# Tractive_System_Board_Rev2.net
KiCad netlist of a schematic drawn in EAGLE
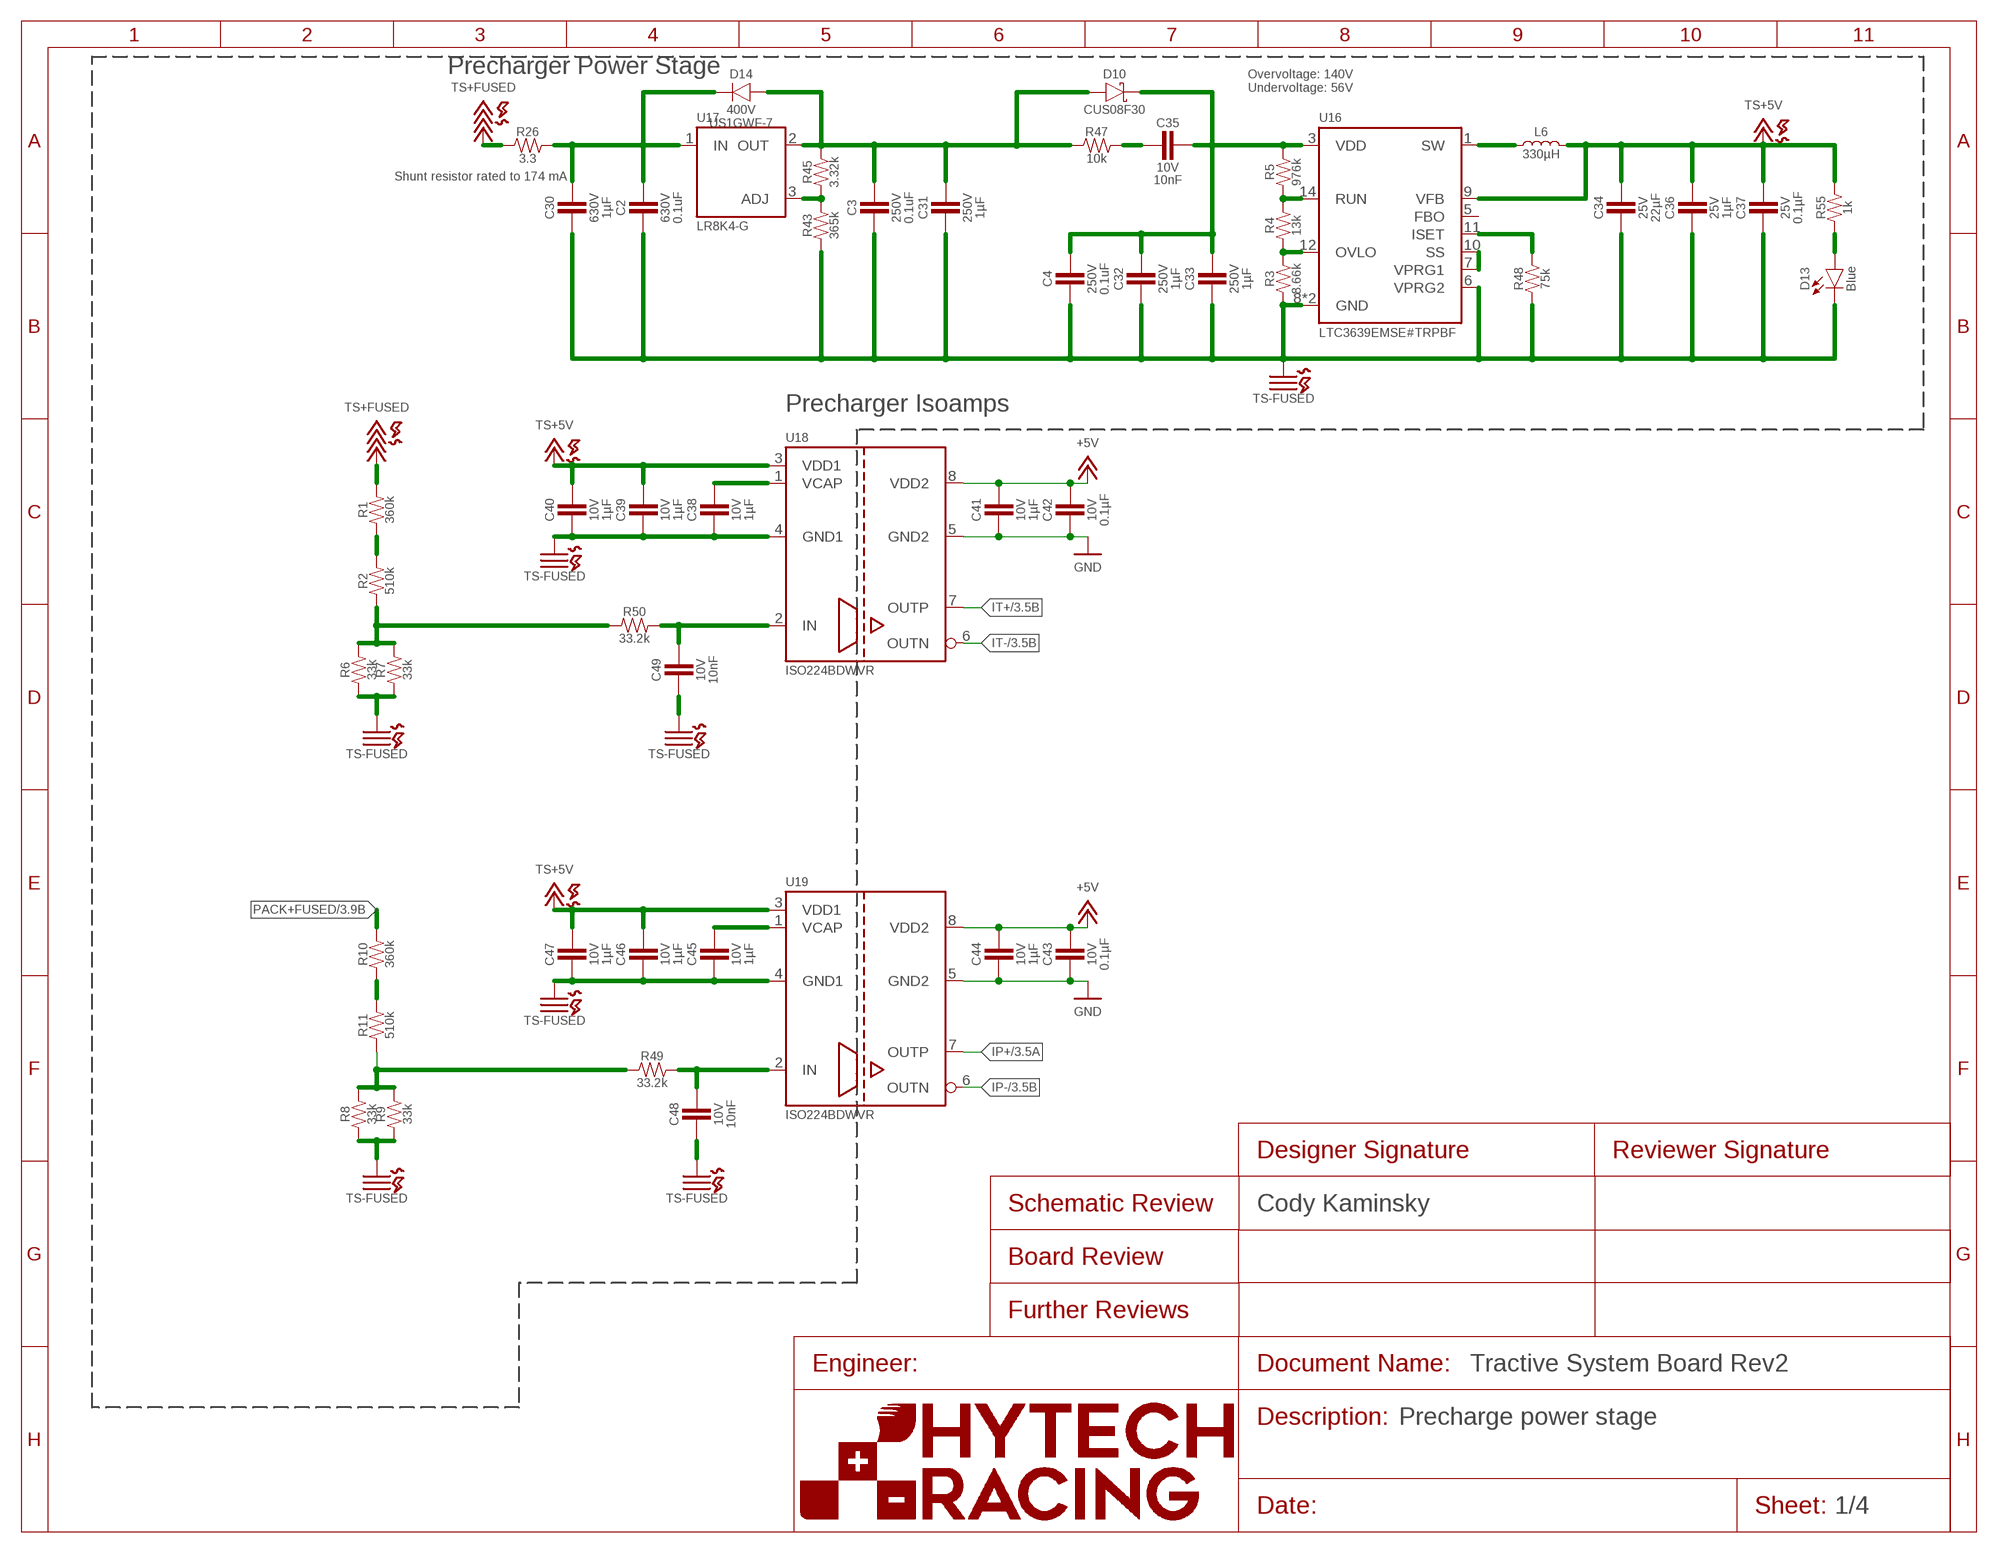
[diagram p0: schematic, sheet 1]
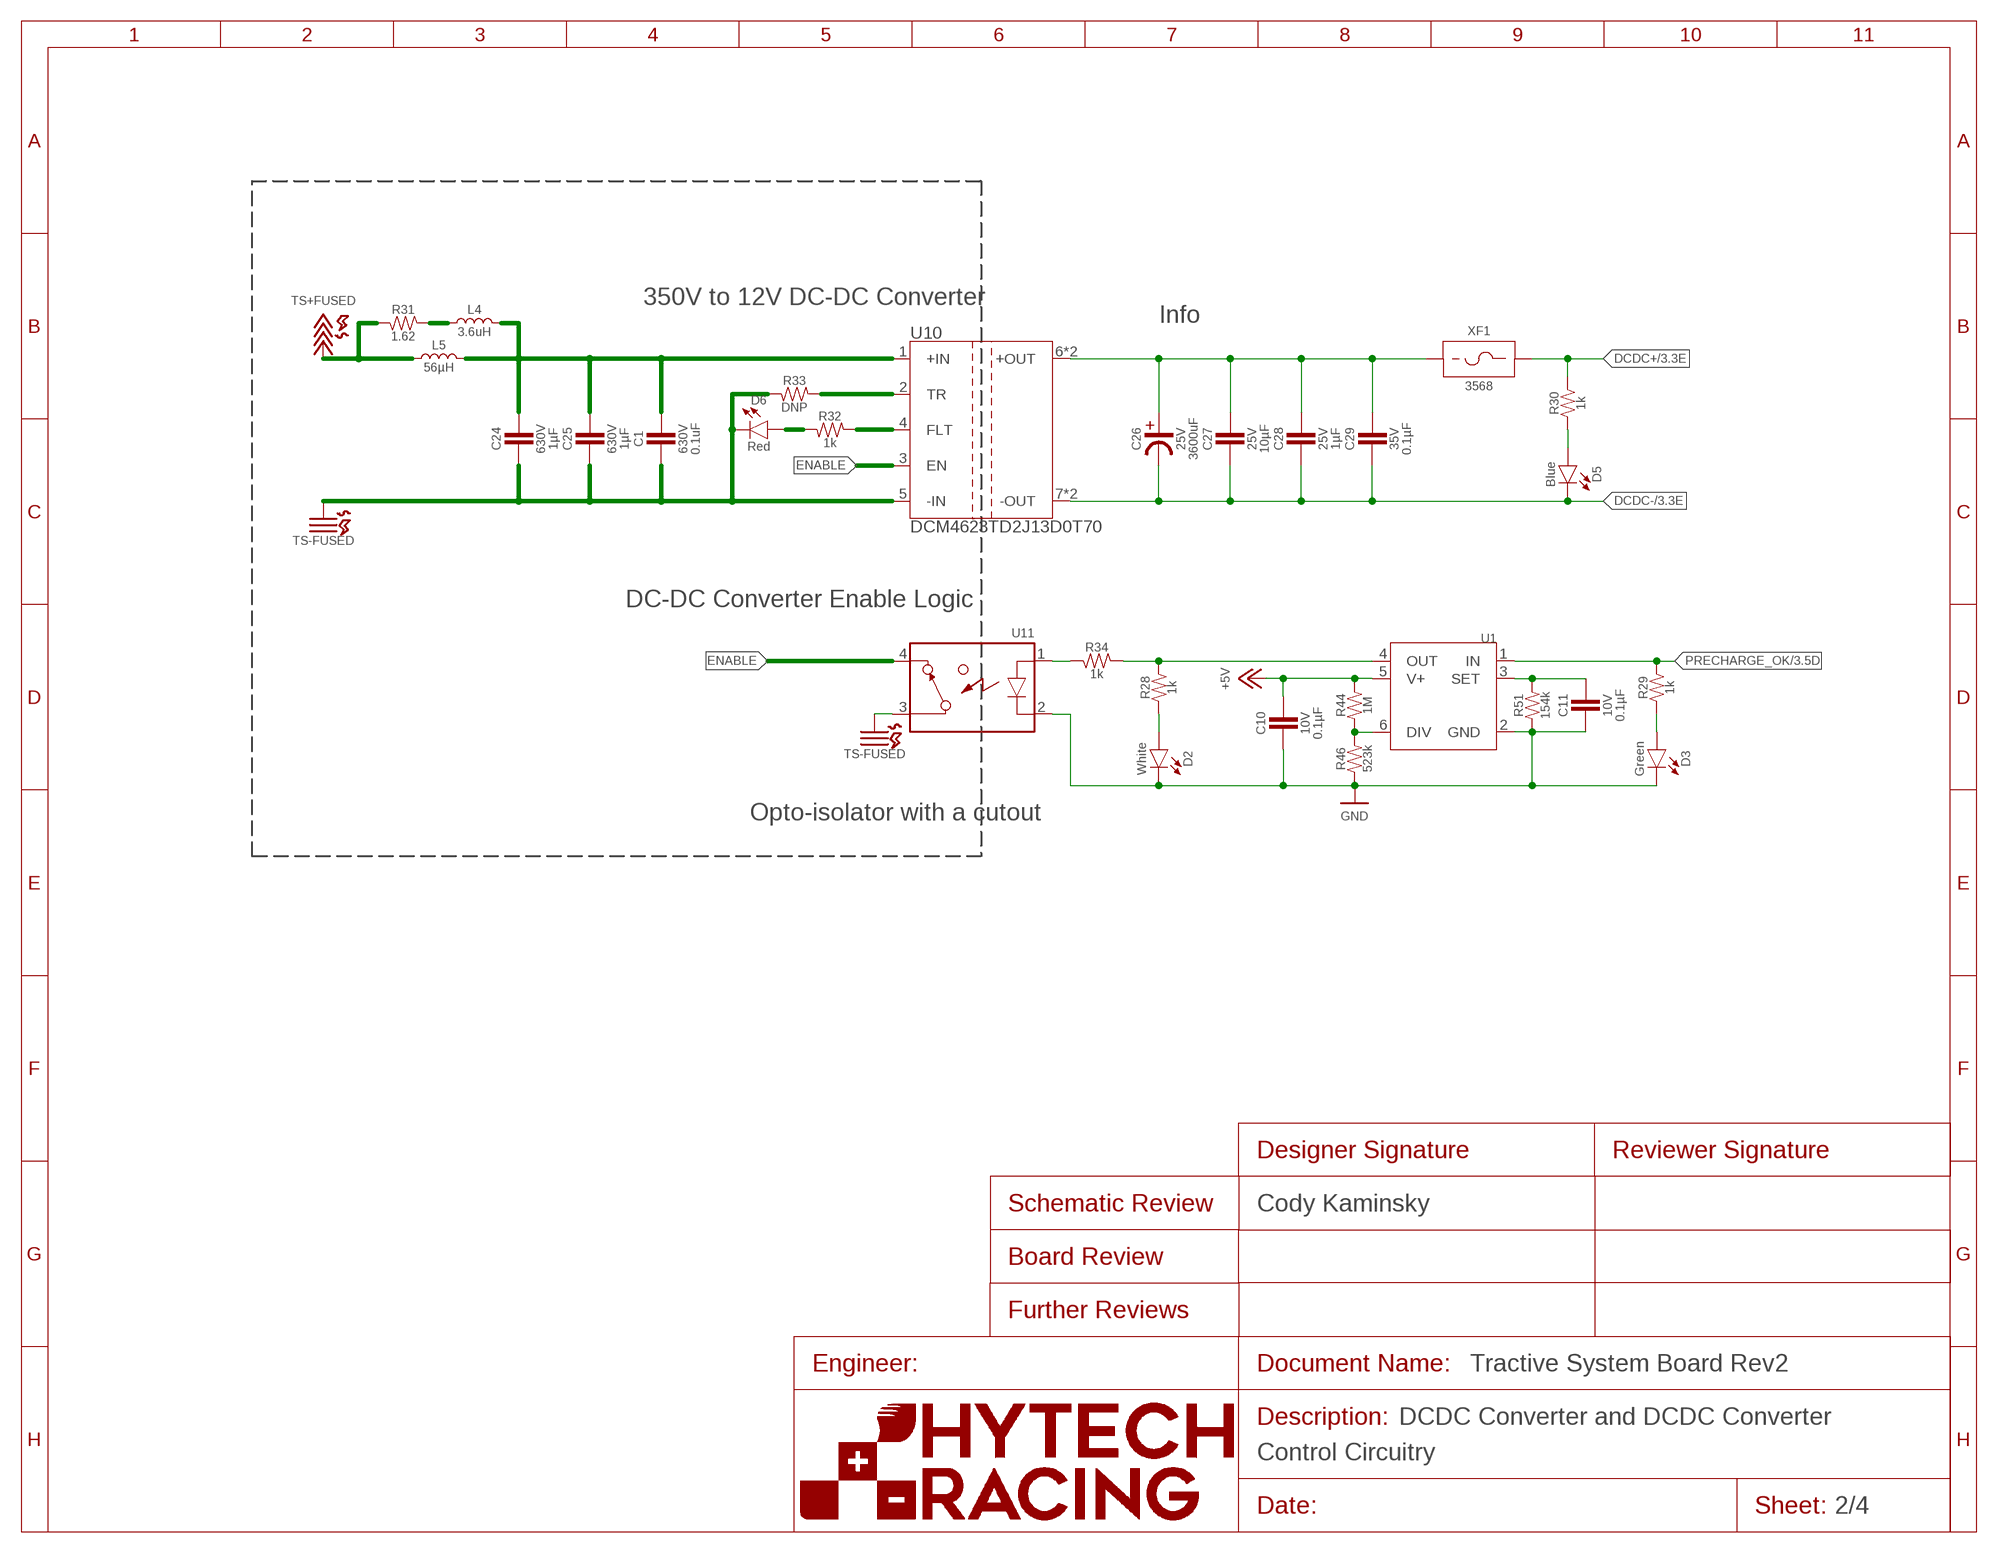
[diagram p1: schematic, sheet 2]
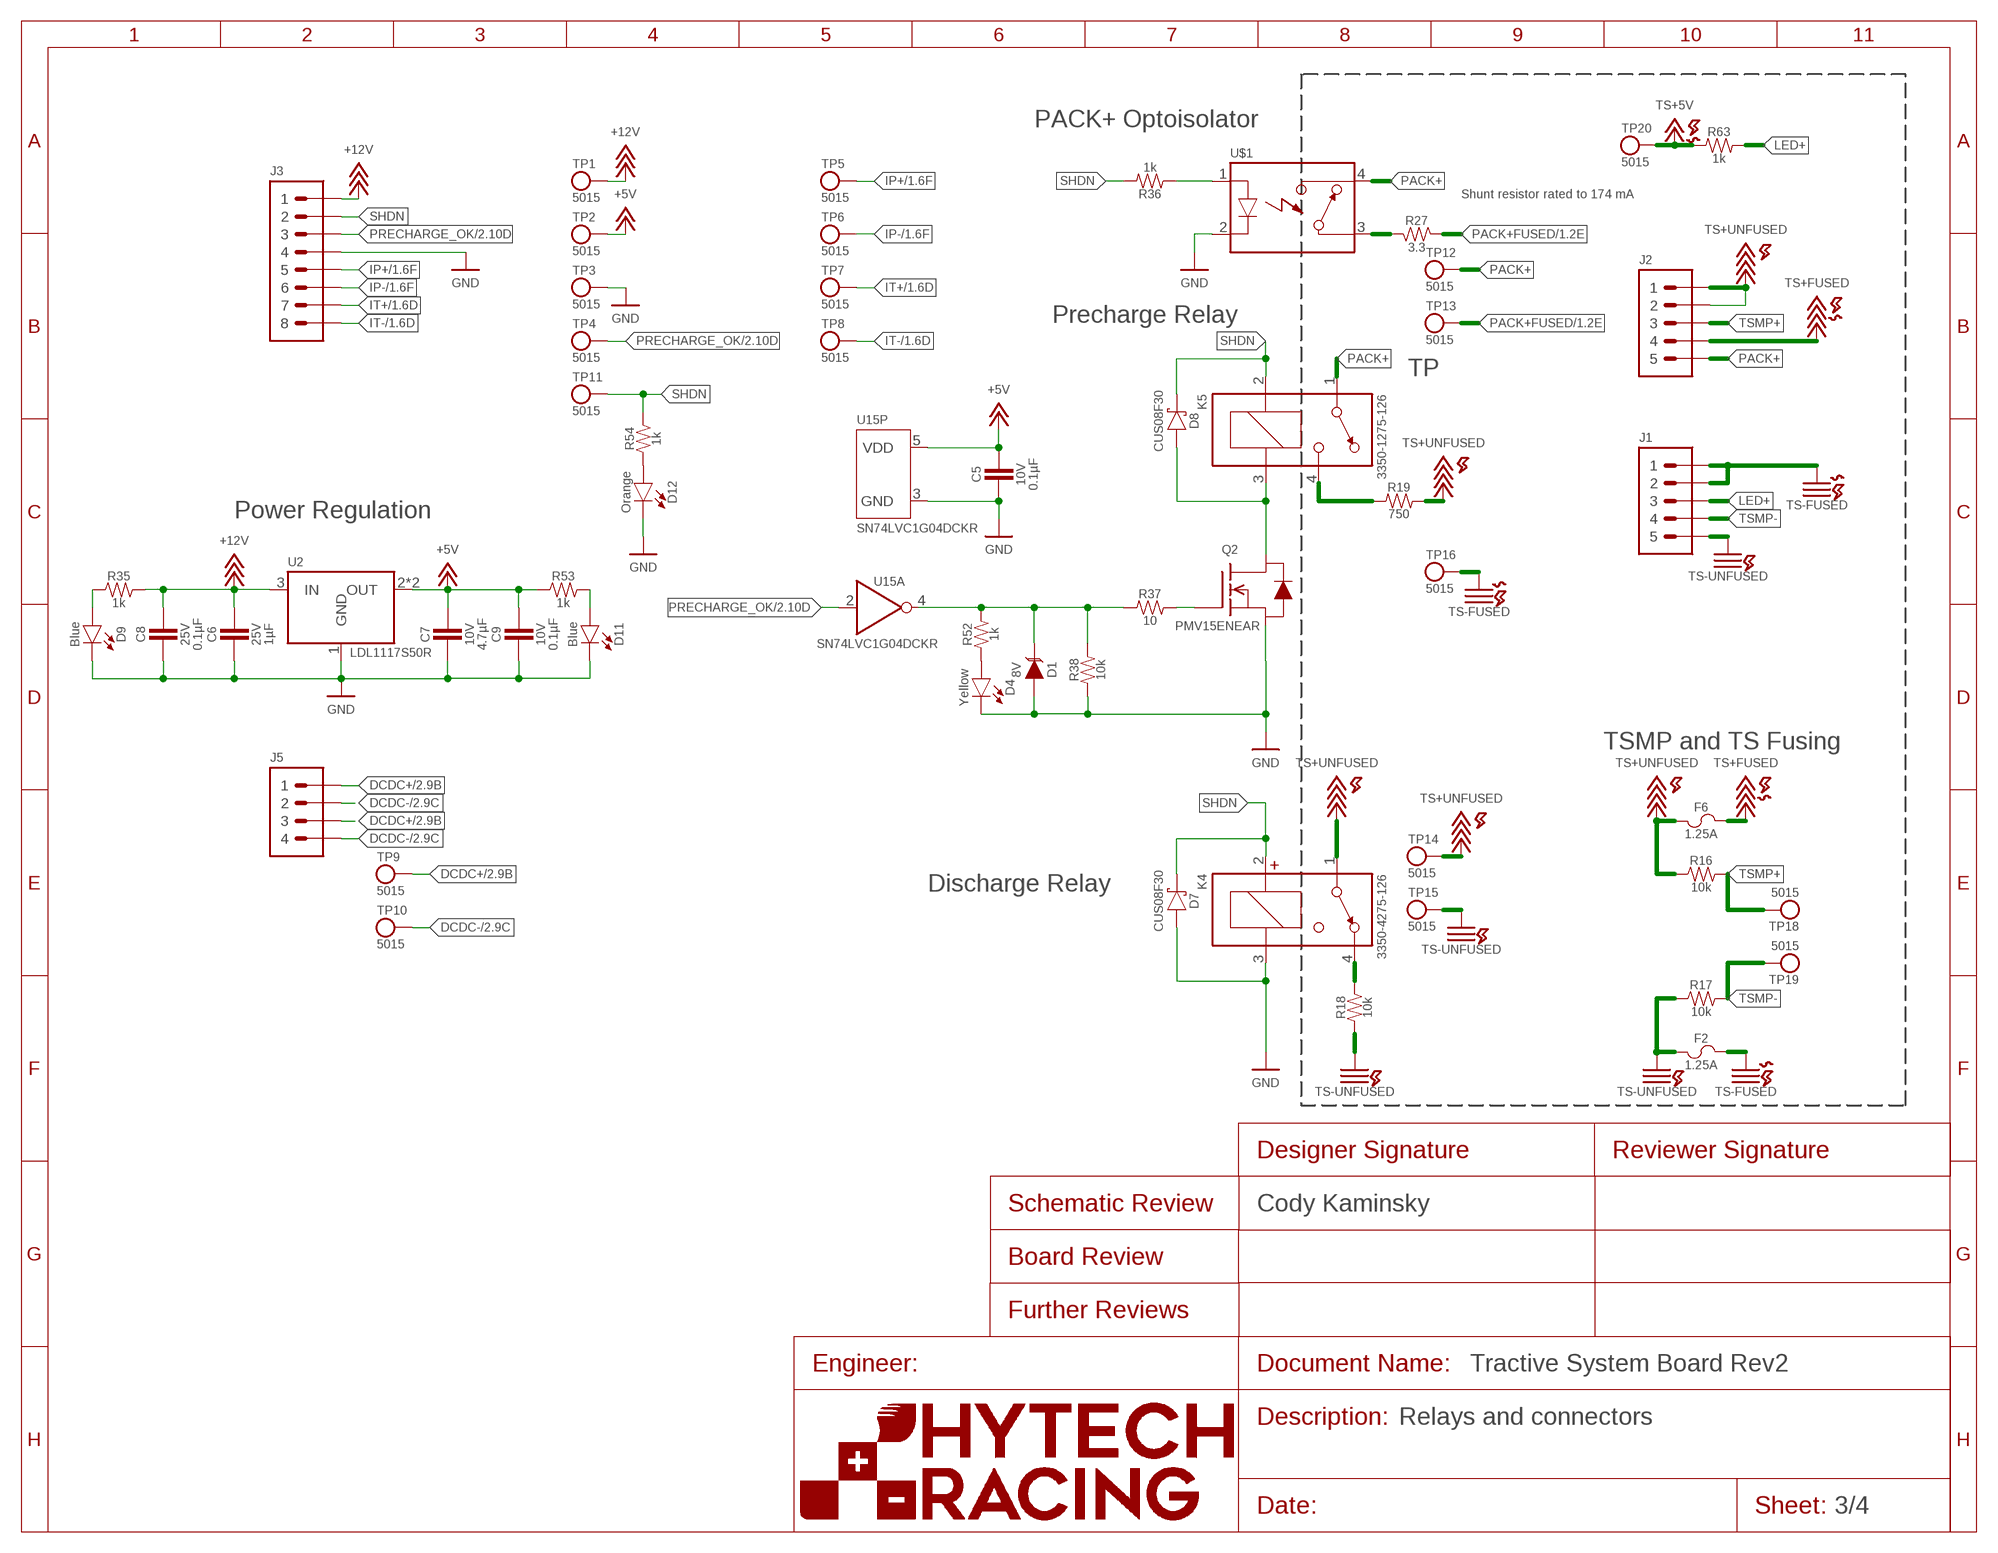
[diagram p2: schematic, sheet 3]
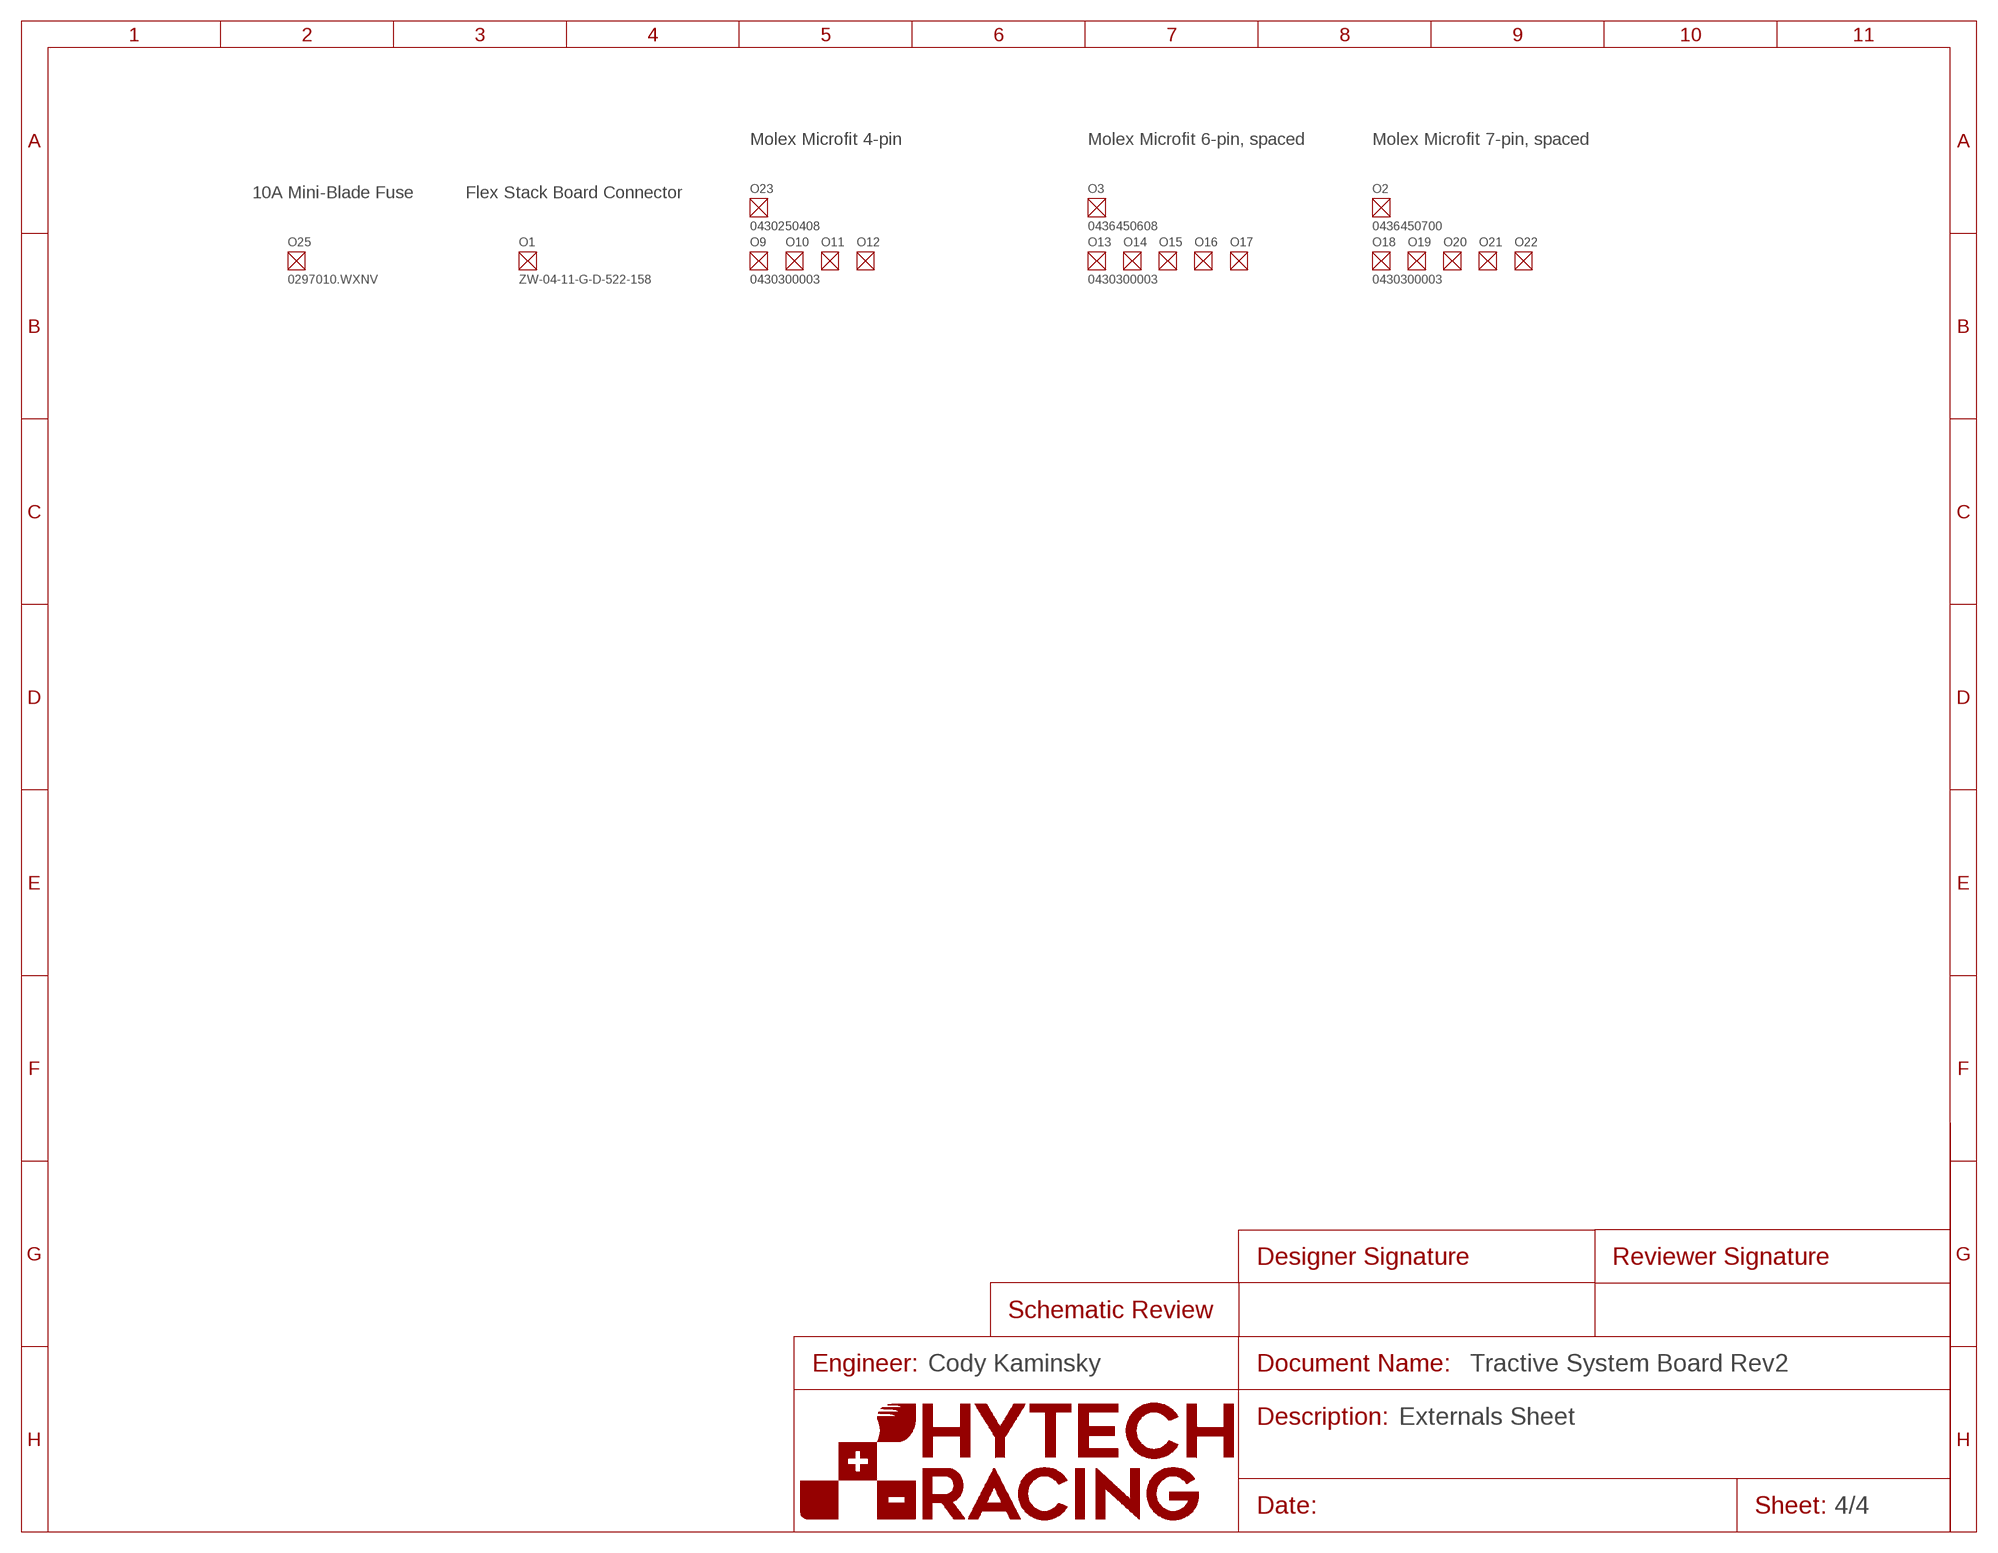
[diagram p3: schematic, sheet 4]

(export (version "E")
  (design (tool "Eeschema 10.0.6"))
  (components
    (comp (ref "C2")
      (value "CAPACITOR_2220_630V_0.1UF")
      (footprint "eagle-import:2220-CAP")
      (fields
        (field (name "CAPACITANCE") "0.1uF")
        (field (name "MANUFACTURER") "TDK Coporation")
        (field (name "MPN") "C5750CH2J104K280KC")
        (field (name "TOLERANCE") "10%")
        (field (name "VOLTAGE") "630V")
      )
      (libsource (lib "eagle-import") (part "CAPACITOR_?_2220630V_0.1UF"))
    )
    (comp (ref "C3")
      (value "CAPACITOR_1206_250V_0.1UF")
      (footprint "eagle-import:1206-CAP")
      (fields
        (field (name "CAPACITANCE") "0.1uF")
        (field (name "MANUFACTURER") "TDK Corporation")
        (field (name "MPN") "C3216X7R2E104K160AM")
        (field (name "TOLERANCE") "10%")
        (field (name "VOLTAGE") "250V")
      )
      (libsource (lib "eagle-import") (part "CAPACITOR_?_1206250V_0.1UF"))
    )
    (comp (ref "C4")
      (value "CAPACITOR_1206_250V_0.1UF")
      (footprint "eagle-import:1206-CAP")
      (fields
        (field (name "CAPACITANCE") "0.1uF")
        (field (name "MANUFACTURER") "TDK Corporation")
        (field (name "MPN") "C3216X7R2E104K160AM")
        (field (name "TOLERANCE") "10%")
        (field (name "VOLTAGE") "250V")
      )
      (libsource (lib "eagle-import") (part "CAPACITOR_?_1206250V_0.1UF"))
    )
    (comp (ref "C30")
      (value "CAPACITOR_2220_630V_1UF")
      (footprint "eagle-import:2220-CAP")
      (fields
        (field (name "CAPACITANCE") "1µF")
        (field (name "MANUFACTURER") "Knowles Syfer")
        (field (name "MPN") "2220Y6300105KXTWS2")
        (field (name "TOLERANCE") "10%")
        (field (name "VOLTAGE") "630V")
      )
      (libsource (lib "eagle-import") (part "CAPACITOR_?_2220630V_1UF"))
    )
    (comp (ref "C31")
      (value "CAPACITOR_2220_250V_1UF")
      (footprint "eagle-import:2220-CAP")
      (fields
        (field (name "CAPACITANCE") "1µF")
        (field (name "MANUFACTURER") "TDK Corporation")
        (field (name "MPN") "C5750X7R2E105K230KA")
        (field (name "TOLERANCE") "10%")
        (field (name "VOLTAGE") "250V")
      )
      (libsource (lib "eagle-import") (part "CAPACITOR_?_2220250V_1UF"))
    )
    (comp (ref "C32")
      (value "CAPACITOR_2220_250V_1UF")
      (footprint "eagle-import:2220-CAP")
      (fields
        (field (name "CAPACITANCE") "1µF")
        (field (name "MANUFACTURER") "TDK Corporation")
        (field (name "MPN") "C5750X7R2E105K230KA")
        (field (name "TOLERANCE") "10%")
        (field (name "VOLTAGE") "250V")
      )
      (libsource (lib "eagle-import") (part "CAPACITOR_?_2220250V_1UF"))
    )
    (comp (ref "C33")
      (value "CAPACITOR_2220_250V_1UF")
      (footprint "eagle-import:2220-CAP")
      (fields
        (field (name "CAPACITANCE") "1µF")
        (field (name "MANUFACTURER") "TDK Corporation")
        (field (name "MPN") "C5750X7R2E105K230KA")
        (field (name "TOLERANCE") "10%")
        (field (name "VOLTAGE") "250V")
      )
      (libsource (lib "eagle-import") (part "CAPACITOR_?_2220250V_1UF"))
    )
    (comp (ref "C34")
      (value "CAPACITOR_0805_25V_22UF")
      (footprint "eagle-import:0805-CAP")
      (fields
        (field (name "CAPACITANCE") "22µF")
        (field (name "MANUFACTURER") "Yageo")
        (field (name "MPN") "CC0805MKX5R8BB226")
        (field (name "TOLERANCE") "20%")
        (field (name "VOLTAGE") "25V")
      )
      (libsource (lib "eagle-import") (part "CAPACITOR_?_080525V_22UF"))
    )
    (comp (ref "C35")
      (value "CAPACITOR_0603_10V_10NF")
      (footprint "eagle-import:0603-CAP")
      (fields
        (field (name "CAPACITANCE") "10nF")
        (field (name "MANUFACTURER") "Yageo")
        (field (name "MPN") "CC0603KRX7R6BB103")
        (field (name "TOLERANCE") "10%")
        (field (name "VOLTAGE") "10V")
      )
      (libsource (lib "eagle-import") (part "CAPACITOR_?_060310V_10NF"))
    )
    (comp (ref "C36")
      (value "CAPACITOR_0603_25V_1UF")
      (footprint "eagle-import:0603-CAP")
      (fields
        (field (name "CAPACITANCE") "1µF")
        (field (name "MANUFACTURER") "Samsung Electro-Mechanics")
        (field (name "MPN") "CL10B105KA8NNNC")
        (field (name "TOLERANCE") "10%")
        (field (name "VOLTAGE") "25V")
      )
      (libsource (lib "eagle-import") (part "CAPACITOR_?_060325V_1UF"))
    )
    (comp (ref "C37")
      (value "CAPACITOR_0603_25V_0.1UF")
      (footprint "eagle-import:0603-CAP")
      (fields
        (field (name "CAPACITANCE") "0.1µF")
        (field (name "MANUFACTURER") "Samsung Electro-Mechanics")
        (field (name "MPN") "CL10B104KA8NNNC")
        (field (name "TOLERANCE") "10%")
        (field (name "VOLTAGE") "25V")
      )
      (libsource (lib "eagle-import") (part "CAPACITOR_?_060325V_0.1UF"))
    )
    (comp (ref "C38")
      (value "CAPACITOR_0603_10V_1UF")
      (footprint "eagle-import:0603-CAP")
      (fields
        (field (name "CAPACITANCE") "1µF")
        (field (name "MANUFACTURER") "Yageo")
        (field (name "MPN") "CC0603KRX7R6BB105")
        (field (name "TOLERANCE") "10%")
        (field (name "VOLTAGE") "10V")
      )
      (libsource (lib "eagle-import") (part "CAPACITOR_?_060310V_1UF"))
    )
    (comp (ref "C39")
      (value "CAPACITOR_0603_10V_1UF")
      (footprint "eagle-import:0603-CAP")
      (fields
        (field (name "CAPACITANCE") "1µF")
        (field (name "MANUFACTURER") "Yageo")
        (field (name "MPN") "CC0603KRX7R6BB105")
        (field (name "TOLERANCE") "10%")
        (field (name "VOLTAGE") "10V")
      )
      (libsource (lib "eagle-import") (part "CAPACITOR_?_060310V_1UF"))
    )
    (comp (ref "C40")
      (value "CAPACITOR_0603_10V_1UF")
      (footprint "eagle-import:0603-CAP")
      (fields
        (field (name "CAPACITANCE") "1µF")
        (field (name "MANUFACTURER") "Yageo")
        (field (name "MPN") "CC0603KRX7R6BB105")
        (field (name "TOLERANCE") "10%")
        (field (name "VOLTAGE") "10V")
      )
      (libsource (lib "eagle-import") (part "CAPACITOR_?_060310V_1UF"))
    )
    (comp (ref "C41")
      (value "CAPACITOR_0603_10V_1UF")
      (footprint "eagle-import:0603-CAP")
      (fields
        (field (name "CAPACITANCE") "1µF")
        (field (name "MANUFACTURER") "Yageo")
        (field (name "MPN") "CC0603KRX7R6BB105")
        (field (name "TOLERANCE") "10%")
        (field (name "VOLTAGE") "10V")
      )
      (libsource (lib "eagle-import") (part "CAPACITOR_?_060310V_1UF"))
    )
    (comp (ref "C42")
      (value "CAPACITOR_0603_10V_0.1UF")
      (footprint "eagle-import:0603-CAP")
      (fields
        (field (name "CAPACITANCE") "0.1µF")
        (field (name "MANUFACTURER") "Vishay Vitramon")
        (field (name "MPN") "VJ0603Y104JXQPW1BC")
        (field (name "TOLERANCE") "5%")
        (field (name "VOLTAGE") "10V")
      )
      (libsource (lib "eagle-import") (part "CAPACITOR_?_060310V_0.1UF"))
    )
    (comp (ref "C43")
      (value "CAPACITOR_0603_10V_0.1UF")
      (footprint "eagle-import:0603-CAP")
      (fields
        (field (name "CAPACITANCE") "0.1µF")
        (field (name "MANUFACTURER") "Vishay Vitramon")
        (field (name "MPN") "VJ0603Y104JXQPW1BC")
        (field (name "TOLERANCE") "5%")
        (field (name "VOLTAGE") "10V")
      )
      (libsource (lib "eagle-import") (part "CAPACITOR_?_060310V_0.1UF"))
    )
    (comp (ref "C44")
      (value "CAPACITOR_0603_10V_1UF")
      (footprint "eagle-import:0603-CAP")
      (fields
        (field (name "CAPACITANCE") "1µF")
        (field (name "MANUFACTURER") "Yageo")
        (field (name "MPN") "CC0603KRX7R6BB105")
        (field (name "TOLERANCE") "10%")
        (field (name "VOLTAGE") "10V")
      )
      (libsource (lib "eagle-import") (part "CAPACITOR_?_060310V_1UF"))
    )
    (comp (ref "C45")
      (value "CAPACITOR_0603_10V_1UF")
      (footprint "eagle-import:0603-CAP")
      (fields
        (field (name "CAPACITANCE") "1µF")
        (field (name "MANUFACTURER") "Yageo")
        (field (name "MPN") "CC0603KRX7R6BB105")
        (field (name "TOLERANCE") "10%")
        (field (name "VOLTAGE") "10V")
      )
      (libsource (lib "eagle-import") (part "CAPACITOR_?_060310V_1UF"))
    )
    (comp (ref "C46")
      (value "CAPACITOR_0603_10V_1UF")
      (footprint "eagle-import:0603-CAP")
      (fields
        (field (name "CAPACITANCE") "1µF")
        (field (name "MANUFACTURER") "Yageo")
        (field (name "MPN") "CC0603KRX7R6BB105")
        (field (name "TOLERANCE") "10%")
        (field (name "VOLTAGE") "10V")
      )
      (libsource (lib "eagle-import") (part "CAPACITOR_?_060310V_1UF"))
    )
    (comp (ref "C47")
      (value "CAPACITOR_0603_10V_1UF")
      (footprint "eagle-import:0603-CAP")
      (fields
        (field (name "CAPACITANCE") "1µF")
        (field (name "MANUFACTURER") "Yageo")
        (field (name "MPN") "CC0603KRX7R6BB105")
        (field (name "TOLERANCE") "10%")
        (field (name "VOLTAGE") "10V")
      )
      (libsource (lib "eagle-import") (part "CAPACITOR_?_060310V_1UF"))
    )
    (comp (ref "C48")
      (value "CAPACITOR_0603_10V_10NF")
      (footprint "eagle-import:0603-CAP")
      (fields
        (field (name "CAPACITANCE") "10nF")
        (field (name "MANUFACTURER") "Yageo")
        (field (name "MPN") "CC0603KRX7R6BB103")
        (field (name "TOLERANCE") "10%")
        (field (name "VOLTAGE") "10V")
      )
      (libsource (lib "eagle-import") (part "CAPACITOR_?_060310V_10NF"))
    )
    (comp (ref "C49")
      (value "CAPACITOR_0603_10V_10NF")
      (footprint "eagle-import:0603-CAP")
      (fields
        (field (name "CAPACITANCE") "10nF")
        (field (name "MANUFACTURER") "Yageo")
        (field (name "MPN") "CC0603KRX7R6BB103")
        (field (name "TOLERANCE") "10%")
        (field (name "VOLTAGE") "10V")
      )
      (libsource (lib "eagle-import") (part "CAPACITOR_?_060310V_10NF"))
    )
    (comp (ref "D10")
      (value "SCHOTTKY_SOD323_30V")
      (footprint "eagle-import:SOD-323")
      (fields
        (field (name "MANUFACTURER") "Toshiba Semiconductor and Storage")
        (field (name "MPN") "CUS08F30")
        (field (name "VOLTAGE") "30V")
      )
      (libsource (lib "eagle-import") (part "SCHOTTKY_?_SOD32330V"))
    )
    (comp (ref "D13")
      (value "LED_0603_BLUE")
      (footprint "eagle-import:0603-LED")
      (fields
        (field (name "COLOR") "Blue")
        (field (name "MANUFACTURER") "Kingbright")
        (field (name "MPN") "APT1608VBC/D")
      )
      (libsource (lib "eagle-import") (part "LED_?_0603BLUE"))
    )
    (comp (ref "D14")
      (value "RECTIFIER_400V_SOD123")
      (footprint "eagle-import:SOD123F")
      (fields
        (field (name "MANUFACTURER") "Diodes Incorporated")
        (field (name "MPN") "US1GWF-7")
        (field (name "VOLTAGE") "400V")
      )
      (libsource (lib "eagle-import") (part "RECTIFIER__?SOD123400V"))
    )
    (comp (ref "L6")
      (value "INDUCTOR_SRU1048_330UH")
      (footprint "eagle-import:SRU1048")
      (fields
        (field (name "INDUCTANCE") "330µH")
        (field (name "MANUFACTURER") "Bourns Inc.")
        (field (name "MPN") "SRU1048-331Y")
        (field (name "TOLERANCE") "30%")
      )
      (libsource (lib "eagle-import") (part "INDUCTOR_?_SRU1048330UH"))
    )
    (comp (ref "R1")
      (value "RESISTOR_0603_360K")
      (footprint "eagle-import:0603-RES")
      (fields
        (field (name "MANUFACTURER") "Rohm Semiconductor")
        (field (name "MPN") "KTR03EZPF3603")
        (field (name "POWER") "0.1W")
        (field (name "RESISTANCE") "360k")
      )
      (libsource (lib "eagle-import") (part "RESISTOR_?_0603360K"))
    )
    (comp (ref "R2")
      (value "RESISTOR_0603_510K")
      (footprint "eagle-import:0603-RES")
      (fields
        (field (name "MANUFACTURER") "Rohm Semiconductor")
        (field (name "MPN") "KTR03EZPF5103")
        (field (name "POWER") "0.1W")
        (field (name "RESISTANCE") "510k")
      )
      (libsource (lib "eagle-import") (part "RESISTOR_?_0603510K"))
    )
    (comp (ref "R3")
      (value "RESISTOR_0603_8.66K")
      (footprint "eagle-import:0603-RES")
      (fields
        (field (name "MANUFACTURER") "Yageo")
        (field (name "MPN") "RT0603BRD078K66L")
        (field (name "POWER") "0.1W")
        (field (name "RESISTANCE") "8.66k")
      )
      (libsource (lib "eagle-import") (part "RESISTOR_?_06038.66K"))
    )
    (comp (ref "R4")
      (value "RESISTOR_0603_13K")
      (footprint "eagle-import:0603-RES")
      (fields
        (field (name "MANUFACTURER") "Panasonic Electronic Components")
        (field (name "MPN") " ERJ-PB3B1302V")
        (field (name "POWER") "0.1W")
        (field (name "RESISTANCE") "13k")
      )
      (libsource (lib "eagle-import") (part "RESISTOR_?_060313K"))
    )
    (comp (ref "R5")
      (value "RESISTOR_0805_976K")
      (footprint "eagle-import:0805-RES")
      (fields
        (field (name "MANUFACTURER") "Panasonic Electronic Components")
        (field (name "MPN") "  ERJ-PB6B9763V")
        (field (name "POWER") "0.25W")
        (field (name "RESISTANCE") "976k")
      )
      (libsource (lib "eagle-import") (part "RESISTOR_?_0805976K"))
    )
    (comp (ref "R6")
      (value "RESISTOR_0603_33K")
      (footprint "eagle-import:0603-RES")
      (fields
        (field (name "MANUFACTURER") "Rohm Semiconductor")
        (field (name "MPN") "KTR03EZPF3302")
        (field (name "POWER") "0.1W")
        (field (name "RESISTANCE") "33k")
      )
      (libsource (lib "eagle-import") (part "RESISTOR_?_060333K"))
    )
    (comp (ref "R7")
      (value "RESISTOR_0603_33K")
      (footprint "eagle-import:0603-RES")
      (fields
        (field (name "MANUFACTURER") "Rohm Semiconductor")
        (field (name "MPN") "KTR03EZPF3302")
        (field (name "POWER") "0.1W")
        (field (name "RESISTANCE") "33k")
      )
      (libsource (lib "eagle-import") (part "RESISTOR_?_060333K"))
    )
    (comp (ref "R8")
      (value "RESISTOR_0603_33K")
      (footprint "eagle-import:0603-RES")
      (fields
        (field (name "MANUFACTURER") "Rohm Semiconductor")
        (field (name "MPN") "KTR03EZPF3302")
        (field (name "POWER") "0.1W")
        (field (name "RESISTANCE") "33k")
      )
      (libsource (lib "eagle-import") (part "RESISTOR_?_060333K"))
    )
    (comp (ref "R9")
      (value "RESISTOR_0603_33K")
      (footprint "eagle-import:0603-RES")
      (fields
        (field (name "MANUFACTURER") "Rohm Semiconductor")
        (field (name "MPN") "KTR03EZPF3302")
        (field (name "POWER") "0.1W")
        (field (name "RESISTANCE") "33k")
      )
      (libsource (lib "eagle-import") (part "RESISTOR_?_060333K"))
    )
    (comp (ref "R10")
      (value "RESISTOR_0603_360K")
      (footprint "eagle-import:0603-RES")
      (fields
        (field (name "MANUFACTURER") "Rohm Semiconductor")
        (field (name "MPN") "KTR03EZPF3603")
        (field (name "POWER") "0.1W")
        (field (name "RESISTANCE") "360k")
      )
      (libsource (lib "eagle-import") (part "RESISTOR_?_0603360K"))
    )
    (comp (ref "R11")
      (value "RESISTOR_0603_510K")
      (footprint "eagle-import:0603-RES")
      (fields
        (field (name "MANUFACTURER") "Rohm Semiconductor")
        (field (name "MPN") "KTR03EZPF5103")
        (field (name "POWER") "0.1W")
        (field (name "RESISTANCE") "510k")
      )
      (libsource (lib "eagle-import") (part "RESISTOR_?_0603510K"))
    )
    (comp (ref "R26")
      (value "RESISTOR_0603_3.3")
      (footprint "eagle-import:0603-RES")
      (fields
        (field (name "MANUFACTURER") "Panasonic Electronic Components")
        (field (name "MPN") "ERJ-3RQF3R3V")
        (field (name "POWER") "0.1W")
        (field (name "RESISTANCE") "3.3")
      )
      (libsource (lib "eagle-import") (part "RESISTOR_?_06033.3"))
    )
    (comp (ref "R43")
      (value "RESISTOR_0805_HV365K")
      (footprint "eagle-import:0805-RES")
      (fields
        (field (name "MANUFACTURER") "Rohm")
        (field (name "MPN") "KTR10EZPF3653")
        (field (name "POWER") "0.125W")
        (field (name "RESISTANCE") "365k")
      )
      (libsource (lib "eagle-import") (part "RESISTOR_?_0805HV365K"))
    )
    (comp (ref "R45")
      (value "RESISTOR_0603_3.32K")
      (footprint "eagle-import:0603-RES")
      (fields
        (field (name "MANUFACTURER") "Yageo")
        (field (name "MPN") "RT0603BRD073K32L")
        (field (name "POWER") "0.1W")
        (field (name "RESISTANCE") "3.32k")
      )
      (libsource (lib "eagle-import") (part "RESISTOR_?_06033.32K"))
    )
    (comp (ref "R47")
      (value "RESISTOR_0603_10K")
      (footprint "eagle-import:0603-RES")
      (fields
        (field (name "MANUFACTURER") "Yageo")
        (field (name "MPN") "RC0603FR-0710KL")
        (field (name "POWER") "0.1W")
        (field (name "RESISTANCE") "10k")
      )
      (libsource (lib "eagle-import") (part "RESISTOR_?_060310K"))
    )
    (comp (ref "R48")
      (value "RESISTOR_0603_75K")
      (footprint "eagle-import:0603-RES")
      (fields
        (field (name "MANUFACTURER") "Yageo")
        (field (name "MPN") "RT0603BRE0775KL")
        (field (name "POWER") "0.1W")
        (field (name "RESISTANCE") "75k")
      )
      (libsource (lib "eagle-import") (part "RESISTOR_?_060375K"))
    )
    (comp (ref "R49")
      (value "RESISTOR_0603_33.2K")
      (footprint "eagle-import:0603-RES")
      (fields
        (field (name "MANUFACTURER") "Panasonic Electronic Components")
        (field (name "MPN") "ERJ-PB3B3322V")
        (field (name "POWER") "0.1W")
        (field (name "RESISTANCE") "33.2k")
      )
      (libsource (lib "eagle-import") (part "RESISTOR_?_060333.2K"))
    )
    (comp (ref "R50")
      (value "RESISTOR_0603_33.2K")
      (footprint "eagle-import:0603-RES")
      (fields
        (field (name "MANUFACTURER") "Panasonic Electronic Components")
        (field (name "MPN") "ERJ-PB3B3322V")
        (field (name "POWER") "0.1W")
        (field (name "RESISTANCE") "33.2k")
      )
      (libsource (lib "eagle-import") (part "RESISTOR_?_060333.2K"))
    )
    (comp (ref "R55")
      (value "RESISTOR_0603_1K")
      (footprint "eagle-import:0603-RES")
      (fields
        (field (name "MANUFACTURER") "Yageo")
        (field (name "MPN") "RC0603FR-071KL")
        (field (name "POWER") "0.1W")
        (field (name "RESISTANCE") "1k")
      )
      (libsource (lib "eagle-import") (part "RESISTOR_?_06031K"))
    )
    (comp (ref "U16")
      (value "LTC3639")
      (footprint "eagle-import:MSE16(12)")
      (fields (field (name "MPN") "LTC3639EMSE#TRPBF ") (field (name "MANUFACTURER") "Analog Devices Inc."))
      (libsource (lib "eagle-import") (part "LTC3639"))
    )
    (comp (ref "U17")
      (value "VOLTAGE_REGULATOR_ADJ_LR8_DPAK")
      (footprint "eagle-import:DPAK(2-7K1S)")
      (fields (field (name "MANUFACTURER") "Microchip Technology") (field (name "MPN") "LR8K4-G"))
      (libsource (lib "eagle-import") (part "VOLTAGE_REGULATOR_ADJ__?DPAKLR8"))
    )
    (comp (ref "U18")
      (value "ISO224B_AIRGAP")
      (footprint "eagle-import:SOIC-08(WIDE,0.295_)-AIRGAP")
      (fields (field (name "MANUFACTURER") "Texas Instruments") (field (name "MPN") "ISO224BDWVR"))
      (libsource (lib "eagle-import") (part "ISO224_AIRGAPB"))
    )
    (comp (ref "U19")
      (value "ISO224B_AIRGAP")
      (footprint "eagle-import:SOIC-08(WIDE,0.295_)-AIRGAP")
      (fields (field (name "MANUFACTURER") "Texas Instruments") (field (name "MPN") "ISO224BDWVR"))
      (libsource (lib "eagle-import") (part "ISO224_AIRGAPB"))
    )
    (comp (ref "C5")
      (value "CAPACITOR_0603_10V_0.1UF")
      (footprint "eagle-import:0603-CAP")
      (fields
        (field (name "CAPACITANCE") "0.1µF")
        (field (name "MANUFACTURER") "Vishay Vitramon")
        (field (name "MPN") "VJ0603Y104JXQPW1BC")
        (field (name "TOLERANCE") "5%")
        (field (name "VOLTAGE") "10V")
      )
      (libsource (lib "eagle-import") (part "CAPACITOR_?_060310V_0.1UF"))
    )
    (comp (ref "C6")
      (value "CAPACITOR_0603_25V_1UF")
      (footprint "eagle-import:0603-CAP")
      (fields
        (field (name "CAPACITANCE") "1µF")
        (field (name "MANUFACTURER") "Samsung Electro-Mechanics")
        (field (name "MPN") "CL10B105KA8NNNC")
        (field (name "TOLERANCE") "10%")
        (field (name "VOLTAGE") "25V")
      )
      (libsource (lib "eagle-import") (part "CAPACITOR_?_060325V_1UF"))
    )
    (comp (ref "C7")
      (value "CAPACITOR_0603_10V_4.7UF")
      (footprint "eagle-import:0603-CAP")
      (fields
        (field (name "CAPACITANCE") "4.7µF")
        (field (name "MANUFACTURER") "Samsung Electro-Mechanics")
        (field (name "MPN") "CL10A475KP8NNNC")
        (field (name "TOLERANCE") "10%")
        (field (name "VOLTAGE") "10V")
      )
      (libsource (lib "eagle-import") (part "CAPACITOR_?_060310V_4.7UF"))
    )
    (comp (ref "C8")
      (value "CAPACITOR_0603_25V_0.1UF")
      (footprint "eagle-import:0603-CAP")
      (fields
        (field (name "CAPACITANCE") "0.1µF")
        (field (name "MANUFACTURER") "Samsung Electro-Mechanics")
        (field (name "MPN") "CL10B104KA8NNNC")
        (field (name "TOLERANCE") "10%")
        (field (name "VOLTAGE") "25V")
      )
      (libsource (lib "eagle-import") (part "CAPACITOR_?_060325V_0.1UF"))
    )
    (comp (ref "C9")
      (value "CAPACITOR_0603_10V_0.1UF")
      (footprint "eagle-import:0603-CAP")
      (fields
        (field (name "CAPACITANCE") "0.1µF")
        (field (name "MANUFACTURER") "Vishay Vitramon")
        (field (name "MPN") "VJ0603Y104JXQPW1BC")
        (field (name "TOLERANCE") "5%")
        (field (name "VOLTAGE") "10V")
      )
      (libsource (lib "eagle-import") (part "CAPACITOR_?_060310V_0.1UF"))
    )
    (comp (ref "D1")
      (value "TVS_8V")
      (footprint "eagle-import:SOT-23")
      (fields
        (field (name "MANUFACTURER") "Vishay General Semiconductor - Diodes Division")
        (field (name "MPN") "GSOT08-E3-08")
        (field (name "VOLTAGE") "8V")
      )
      (libsource (lib "eagle-import") (part "TVS_8V"))
    )
    (comp (ref "D4")
      (value "LED_0603_YELLOW")
      (footprint "eagle-import:0603-LED")
      (fields
        (field (name "COLOR") "Yellow")
        (field (name "MANUFACTURER") "Kingbright")
        (field (name "MPN") "APT1608SYCK/J3-PRV")
      )
      (libsource (lib "eagle-import") (part "LED_?_0603YELLOW"))
    )
    (comp (ref "D7")
      (value "SCHOTTKY_SOD323_30V")
      (footprint "eagle-import:SOD-323")
      (fields
        (field (name "MANUFACTURER") "Toshiba Semiconductor and Storage")
        (field (name "MPN") "CUS08F30")
        (field (name "VOLTAGE") "30V")
      )
      (libsource (lib "eagle-import") (part "SCHOTTKY_?_SOD32330V"))
    )
    (comp (ref "D8")
      (value "SCHOTTKY_SOD323_30V")
      (footprint "eagle-import:SOD-323")
      (fields
        (field (name "MANUFACTURER") "Toshiba Semiconductor and Storage")
        (field (name "MPN") "CUS08F30")
        (field (name "VOLTAGE") "30V")
      )
      (libsource (lib "eagle-import") (part "SCHOTTKY_?_SOD32330V"))
    )
    (comp (ref "D9")
      (value "LED_0603_BLUE")
      (footprint "eagle-import:0603-LED")
      (fields
        (field (name "COLOR") "Blue")
        (field (name "MANUFACTURER") "Kingbright")
        (field (name "MPN") "APT1608VBC/D")
      )
      (libsource (lib "eagle-import") (part "LED_?_0603BLUE"))
    )
    (comp (ref "D11")
      (value "LED_0603_BLUE")
      (footprint "eagle-import:0603-LED")
      (fields
        (field (name "COLOR") "Blue")
        (field (name "MANUFACTURER") "Kingbright")
        (field (name "MPN") "APT1608VBC/D")
      )
      (libsource (lib "eagle-import") (part "LED_?_0603BLUE"))
    )
    (comp (ref "D12")
      (value "LED_0603_ORANGE")
      (footprint "eagle-import:0603-LED")
      (fields
        (field (name "COLOR") "Orange")
        (field (name "MANUFACTURER") "Kingbright")
        (field (name "MPN") "APT1608SECK")
      )
      (libsource (lib "eagle-import") (part "LED_?_0603ORANGE"))
    )
    (comp (ref "F2")
      (value "FUSE_0885_1.25")
      (footprint "eagle-import:0885")
      (fields
        (field (name "CURRENT") "1.25A")
        (field (name "MANUFACTURER") "Littelfuse Inc.")
        (field (name "MPN") "08851.25DR")
        (field (name "VOLTAGE") "500V")
      )
      (libsource (lib "eagle-import") (part "FUSE_?_08851.25"))
    )
    (comp (ref "F6")
      (value "FUSE_0885_1.25")
      (footprint "eagle-import:0885")
      (fields
        (field (name "CURRENT") "1.25A")
        (field (name "MANUFACTURER") "Littelfuse Inc.")
        (field (name "MPN") "08851.25DR")
        (field (name "VOLTAGE") "500V")
      )
      (libsource (lib "eagle-import") (part "FUSE_?_08851.25"))
    )
    (comp (ref "J1")
      (value "CONNECTOR-5_MICRO_V6S_")
      (footprint "eagle-import:MOLEX_MICROFIT_PTH_VERTICAL_06_SINGLE_SPACED")
      (fields (field (name "MPN") "2165713006") (field (name "MANUFACTURER") "Molex"))
      (libsource (lib "eagle-import") (part "CONNECTOR-5_?_MICRO_V6S"))
    )
    (comp (ref "J2")
      (value "CONNECTOR-5_MICRO_V7S_")
      (footprint "eagle-import:MOLEX_MICROFIT_PTH_VERTICAL_07_SINGLE_SPACED")
      (fields (field (name "MPN") "2165713007") (field (name "MANUFACTURER") "Molex"))
      (libsource (lib "eagle-import") (part "CONNECTOR-5_?_MICRO_V7S"))
    )
    (comp (ref "J3")
      (value "CONNECTOR-8_S_S")
      (footprint "eagle-import:FLEX_STACK_PTH_08_DUAL")
      (fields
        (field (name "MANUFACTURER") "Sullins Connector Solutions")
        (field (name "MPN") "PPPC042LFBN-RC")
      )
      (libsource (lib "eagle-import") (part "CONNECTOR-8_?_SS"))
    )
    (comp (ref "J5")
      (value "CONNECTOR-4__")
      (footprint "eagle-import:MOLEX_MICROFIT_PTH_VERTICAL_04_DUAL")
      (fields (field (name "MPN") "2068320423") (field (name "MANUFACTURER") "Molex"))
      (libsource (lib "eagle-import") (part "CONNECTOR-4_?_"))
    )
    (comp (ref "K4")
      (value "RELAY_SPST_NC_POLARIZED_3550_12")
      (footprint "eagle-import:335X")
      (fields (field (name "MANUFACTURER") "Comus International") (field (name "MPN") "3350-4275-126"))
      (libsource (lib "eagle-import") (part "RELAY_SPST_NC_POLARIZED_?3550_12"))
    )
    (comp (ref "K5")
      (value "RELAY_SPST_NO_3550_12")
      (footprint "eagle-import:335X")
      (fields (field (name "MANUFACTURER") "Comus International") (field (name "MPN") "3350-1275-126"))
      (libsource (lib "eagle-import") (part "RELAY_SPST_NO_?3550_12"))
    )
    (comp (ref "Q2")
      (value "TRANSISTOR_N_MOS__PMV15ENEA")
      (footprint "eagle-import:SOT-23")
      (fields (field (name "MANUFACTURER") "Nexperia USA Inc.") (field (name "MPN") "PMV15ENEAR"))
      (libsource (lib "eagle-import") (part "TRANSISTOR_N_MOS_?_PMV15ENEA"))
    )
    (comp (ref "R16")
      (value "RESISTOR_B20_10K")
      (footprint "eagle-import:B20")
      (fields
        (field (name "MANUFACTURER") "Ohmite")
        (field (name "MPN") "B20J10KE")
        (field (name "POWER") "20W")
        (field (name "RESISTANCE") "10k")
      )
      (libsource (lib "eagle-import") (part "RESISTOR_?_B2010K"))
    )
    (comp (ref "R17")
      (value "RESISTOR_B20_10K")
      (footprint "eagle-import:B20")
      (fields
        (field (name "MANUFACTURER") "Ohmite")
        (field (name "MPN") "B20J10KE")
        (field (name "POWER") "20W")
        (field (name "RESISTANCE") "10k")
      )
      (libsource (lib "eagle-import") (part "RESISTOR_?_B2010K"))
    )
    (comp (ref "R18")
      (value "RESISTOR_B20_10K")
      (footprint "eagle-import:B20")
      (fields
        (field (name "MANUFACTURER") "Ohmite")
        (field (name "MPN") "B20J10KE")
        (field (name "POWER") "20W")
        (field (name "RESISTANCE") "10k")
      )
      (libsource (lib "eagle-import") (part "RESISTOR_?_B2010K"))
    )
    (comp (ref "R19")
      (value "RESISTOR_B20_750")
      (footprint "eagle-import:B20")
      (fields
        (field (name "MANUFACTURER") "Ohmite")
        (field (name "MPN") "B20J750E")
        (field (name "POWER") "20W")
        (field (name "RESISTANCE") "750")
      )
      (libsource (lib "eagle-import") (part "RESISTOR_?_B20750"))
    )
    (comp (ref "R27")
      (value "RESISTOR_0603_3.3")
      (footprint "eagle-import:0603-RES")
      (fields
        (field (name "MANUFACTURER") "Panasonic Electronic Components")
        (field (name "MPN") "ERJ-3RQF3R3V")
        (field (name "POWER") "0.1W")
        (field (name "RESISTANCE") "3.3")
      )
      (libsource (lib "eagle-import") (part "RESISTOR_?_06033.3"))
    )
    (comp (ref "R35")
      (value "RESISTOR_0603_1K")
      (footprint "eagle-import:0603-RES")
      (fields
        (field (name "MANUFACTURER") "Yageo")
        (field (name "MPN") "RC0603FR-071KL")
        (field (name "POWER") "0.1W")
        (field (name "RESISTANCE") "1k")
      )
      (libsource (lib "eagle-import") (part "RESISTOR_?_06031K"))
    )
    (comp (ref "R36")
      (value "RESISTOR_0603_1K")
      (footprint "eagle-import:0603-RES")
      (fields
        (field (name "MANUFACTURER") "Yageo")
        (field (name "MPN") "RC0603FR-071KL")
        (field (name "POWER") "0.1W")
        (field (name "RESISTANCE") "1k")
      )
      (libsource (lib "eagle-import") (part "RESISTOR_?_06031K"))
    )
    (comp (ref "R37")
      (value "RESISTOR_0603_10")
      (footprint "eagle-import:0603-RES")
      (fields
        (field (name "MANUFACTURER") "Yageo")
        (field (name "MPN") "RC0603FR-0710RL")
        (field (name "POWER") "0.1W")
        (field (name "RESISTANCE") "10")
      )
      (libsource (lib "eagle-import") (part "RESISTOR_?_060310"))
    )
    (comp (ref "R38")
      (value "RESISTOR_0603_10K")
      (footprint "eagle-import:0603-RES")
      (fields
        (field (name "MANUFACTURER") "Yageo")
        (field (name "MPN") "RC0603FR-0710KL")
        (field (name "POWER") "0.1W")
        (field (name "RESISTANCE") "10k")
      )
      (libsource (lib "eagle-import") (part "RESISTOR_?_060310K"))
    )
    (comp (ref "R52")
      (value "RESISTOR_0603_1K")
      (footprint "eagle-import:0603-RES")
      (fields
        (field (name "MANUFACTURER") "Yageo")
        (field (name "MPN") "RC0603FR-071KL")
        (field (name "POWER") "0.1W")
        (field (name "RESISTANCE") "1k")
      )
      (libsource (lib "eagle-import") (part "RESISTOR_?_06031K"))
    )
    (comp (ref "R53")
      (value "RESISTOR_0603_1K")
      (footprint "eagle-import:0603-RES")
      (fields
        (field (name "MANUFACTURER") "Yageo")
        (field (name "MPN") "RC0603FR-071KL")
        (field (name "POWER") "0.1W")
        (field (name "RESISTANCE") "1k")
      )
      (libsource (lib "eagle-import") (part "RESISTOR_?_06031K"))
    )
    (comp (ref "R54")
      (value "RESISTOR_0603_1K")
      (footprint "eagle-import:0603-RES")
      (fields
        (field (name "MANUFACTURER") "Yageo")
        (field (name "MPN") "RC0603FR-071KL")
        (field (name "POWER") "0.1W")
        (field (name "RESISTANCE") "1k")
      )
      (libsource (lib "eagle-import") (part "RESISTOR_?_06031K"))
    )
    (comp (ref "R63")
      (value "RESISTOR_0603_1K")
      (footprint "eagle-import:0603-RES")
      (fields
        (field (name "MANUFACTURER") "Yageo")
        (field (name "MPN") "RC0603FR-071KL")
        (field (name "POWER") "0.1W")
        (field (name "RESISTANCE") "1k")
      )
      (libsource (lib "eagle-import") (part "RESISTOR_?_06031K"))
    )
    (comp (ref "TP1")
      (value "TEST_POINT")
      (footprint "eagle-import:MICRO_MINIATURE")
      (fields (field (name "MPN") "5015") (field (name "MANUFACTURER") "Keystone Electronics"))
      (libsource (lib "eagle-import") (part "TEST_POINT"))
    )
    (comp (ref "TP2")
      (value "TEST_POINT")
      (footprint "eagle-import:MICRO_MINIATURE")
      (fields (field (name "MPN") "5015") (field (name "MANUFACTURER") "Keystone Electronics"))
      (libsource (lib "eagle-import") (part "TEST_POINT"))
    )
    (comp (ref "TP3")
      (value "TEST_POINT")
      (footprint "eagle-import:MICRO_MINIATURE")
      (fields (field (name "MPN") "5015") (field (name "MANUFACTURER") "Keystone Electronics"))
      (libsource (lib "eagle-import") (part "TEST_POINT"))
    )
    (comp (ref "TP4")
      (value "TEST_POINT")
      (footprint "eagle-import:MICRO_MINIATURE")
      (fields (field (name "MPN") "5015") (field (name "MANUFACTURER") "Keystone Electronics"))
      (libsource (lib "eagle-import") (part "TEST_POINT"))
    )
    (comp (ref "TP5")
      (value "TEST_POINT")
      (footprint "eagle-import:MICRO_MINIATURE")
      (fields (field (name "MPN") "5015") (field (name "MANUFACTURER") "Keystone Electronics"))
      (libsource (lib "eagle-import") (part "TEST_POINT"))
    )
    (comp (ref "TP6")
      (value "TEST_POINT")
      (footprint "eagle-import:MICRO_MINIATURE")
      (fields (field (name "MPN") "5015") (field (name "MANUFACTURER") "Keystone Electronics"))
      (libsource (lib "eagle-import") (part "TEST_POINT"))
    )
    (comp (ref "TP7")
      (value "TEST_POINT")
      (footprint "eagle-import:MICRO_MINIATURE")
      (fields (field (name "MPN") "5015") (field (name "MANUFACTURER") "Keystone Electronics"))
      (libsource (lib "eagle-import") (part "TEST_POINT"))
    )
    (comp (ref "TP8")
      (value "TEST_POINT")
      (footprint "eagle-import:MICRO_MINIATURE")
      (fields (field (name "MPN") "5015") (field (name "MANUFACTURER") "Keystone Electronics"))
      (libsource (lib "eagle-import") (part "TEST_POINT"))
    )
    (comp (ref "TP9")
      (value "TEST_POINT")
      (footprint "eagle-import:MICRO_MINIATURE")
      (fields (field (name "MPN") "5015") (field (name "MANUFACTURER") "Keystone Electronics"))
      (libsource (lib "eagle-import") (part "TEST_POINT"))
    )
    (comp (ref "TP10")
      (value "TEST_POINT")
      (footprint "eagle-import:MICRO_MINIATURE")
      (fields (field (name "MPN") "5015") (field (name "MANUFACTURER") "Keystone Electronics"))
      (libsource (lib "eagle-import") (part "TEST_POINT"))
    )
    (comp (ref "TP11")
      (value "TEST_POINT")
      (footprint "eagle-import:MICRO_MINIATURE")
      (fields (field (name "MPN") "5015") (field (name "MANUFACTURER") "Keystone Electronics"))
      (libsource (lib "eagle-import") (part "TEST_POINT"))
    )
    (comp (ref "TP12")
      (value "TEST_POINT")
      (footprint "eagle-import:MICRO_MINIATURE")
      (fields (field (name "MPN") "5015") (field (name "MANUFACTURER") "Keystone Electronics"))
      (libsource (lib "eagle-import") (part "TEST_POINT"))
    )
    (comp (ref "TP13")
      (value "TEST_POINT")
      (footprint "eagle-import:MICRO_MINIATURE")
      (fields (field (name "MPN") "5015") (field (name "MANUFACTURER") "Keystone Electronics"))
      (libsource (lib "eagle-import") (part "TEST_POINT"))
    )
    (comp (ref "TP14")
      (value "TEST_POINT")
      (footprint "eagle-import:MICRO_MINIATURE")
      (fields (field (name "MPN") "5015") (field (name "MANUFACTURER") "Keystone Electronics"))
      (libsource (lib "eagle-import") (part "TEST_POINT"))
    )
    (comp (ref "TP15")
      (value "TEST_POINT")
      (footprint "eagle-import:MICRO_MINIATURE")
      (fields (field (name "MPN") "5015") (field (name "MANUFACTURER") "Keystone Electronics"))
      (libsource (lib "eagle-import") (part "TEST_POINT"))
    )
    (comp (ref "TP16")
      (value "TEST_POINT")
      (footprint "eagle-import:MICRO_MINIATURE")
      (fields (field (name "MPN") "5015") (field (name "MANUFACTURER") "Keystone Electronics"))
      (libsource (lib "eagle-import") (part "TEST_POINT"))
    )
    (comp (ref "TP18")
      (value "TEST_POINT")
      (footprint "eagle-import:MICRO_MINIATURE")
      (fields (field (name "MPN") "5015") (field (name "MANUFACTURER") "Keystone Electronics"))
      (libsource (lib "eagle-import") (part "TEST_POINT"))
    )
    (comp (ref "TP19")
      (value "TEST_POINT")
      (footprint "eagle-import:MICRO_MINIATURE")
      (fields (field (name "MPN") "5015") (field (name "MANUFACTURER") "Keystone Electronics"))
      (libsource (lib "eagle-import") (part "TEST_POINT"))
    )
    (comp (ref "TP20")
      (value "TEST_POINT")
      (footprint "eagle-import:MICRO_MINIATURE")
      (fields (field (name "MPN") "5015") (field (name "MANUFACTURER") "Keystone Electronics"))
      (libsource (lib "eagle-import") (part "TEST_POINT"))
    )
    (comp (ref "U$1")
      (value "RELAY_SOLIDSTATE_NO")
      (footprint "eagle-import:DIP-4")
      (fields (field (name "MPN") "AQY214EHA"))
      (libsource (lib "eagle-import") (part "RELAY_SOLIDSTATE_NO"))
    )
    (comp (ref "U2")
      (value "VOLTAGE_REGULATOR_SOT223_5V")
      (footprint "eagle-import:SOT223")
      (fields (field (name "MANUFACTURER") "STMicroelectronics") (field (name "MPN") "LDL1117S50R"))
      (libsource (lib "eagle-import") (part "VOLTAGE_REGULATOR_?_SOT2235V"))
    )
    (comp (ref "U15")
      (value "LOGICGATE_INVERTER_DCKR")
      (footprint "eagle-import:SC-70-5")
      (fields (field (name "MANUFACTURER") "Texas Instruments") (field (name "MPN") "SN74LVC1G04DCKR"))
      (libsource (lib "eagle-import") (part "LOGICGATE_INVERTER_DCKR"))
    )
    (comp (ref "C1")
      (value "CAPACITOR_2220_630V_0.1UF")
      (footprint "eagle-import:2220-CAP")
      (fields
        (field (name "CAPACITANCE") "0.1uF")
        (field (name "MANUFACTURER") "TDK Coporation")
        (field (name "MPN") "C5750CH2J104K280KC")
        (field (name "TOLERANCE") "10%")
        (field (name "VOLTAGE") "630V")
      )
      (libsource (lib "eagle-import") (part "CAPACITOR_?_2220630V_0.1UF"))
    )
    (comp (ref "C10")
      (value "CAPACITOR_0603_10V_0.1UF")
      (footprint "eagle-import:0603-CAP")
      (fields
        (field (name "CAPACITANCE") "0.1µF")
        (field (name "MANUFACTURER") "Vishay Vitramon")
        (field (name "MPN") "VJ0603Y104JXQPW1BC")
        (field (name "TOLERANCE") "5%")
        (field (name "VOLTAGE") "10V")
      )
      (libsource (lib "eagle-import") (part "CAPACITOR_?_060310V_0.1UF"))
    )
    (comp (ref "C11")
      (value "CAPACITOR_0603_10V_0.1UF")
      (footprint "eagle-import:0603-CAP")
      (fields
        (field (name "CAPACITANCE") "0.1µF")
        (field (name "MANUFACTURER") "Vishay Vitramon")
        (field (name "MPN") "VJ0603Y104JXQPW1BC")
        (field (name "TOLERANCE") "5%")
        (field (name "VOLTAGE") "10V")
      )
      (libsource (lib "eagle-import") (part "CAPACITOR_?_060310V_0.1UF"))
    )
    (comp (ref "C24")
      (value "CAPACITOR_2220_630V_1UF")
      (footprint "eagle-import:2220-CAP")
      (fields
        (field (name "CAPACITANCE") "1µF")
        (field (name "MANUFACTURER") "Knowles Syfer")
        (field (name "MPN") "2220Y6300105KXTWS2")
        (field (name "TOLERANCE") "10%")
        (field (name "VOLTAGE") "630V")
      )
      (libsource (lib "eagle-import") (part "CAPACITOR_?_2220630V_1UF"))
    )
    (comp (ref "C25")
      (value "CAPACITOR_2220_630V_1UF")
      (footprint "eagle-import:2220-CAP")
      (fields
        (field (name "CAPACITANCE") "1µF")
        (field (name "MANUFACTURER") "Knowles Syfer")
        (field (name "MPN") "2220Y6300105KXTWS2")
        (field (name "TOLERANCE") "10%")
        (field (name "VOLTAGE") "630V")
      )
      (libsource (lib "eagle-import") (part "CAPACITOR_?_2220630V_1UF"))
    )
    (comp (ref "C26")
      (value "CAPACITOR_POLAR__3600UF")
      (footprint "eagle-import:EKYC_MM")
      (fields
        (field (name "CAPACITANCE") "3600uF")
        (field (name "MANUFACTURER") "United Chemi-con")
        (field (name "MPN") "EKYC250ELL362ML20S")
        (field (name "VOLTAGE") "25V")
      )
      (libsource (lib "eagle-import") (part "CAPACITOR_POLAR_?_3600UF"))
    )
    (comp (ref "C27")
      (value "CAPACITOR_0603_25V_10UF")
      (footprint "eagle-import:0603-CAP")
      (fields
        (field (name "CAPACITANCE") "10µF")
        (field (name "MANUFACTURER") "Murata Electronics")
        (field (name "MPN") "GRM188R61E106MA73D")
        (field (name "TOLERANCE") "20%")
        (field (name "VOLTAGE") "25V")
      )
      (libsource (lib "eagle-import") (part "CAPACITOR_?_060325V_10UF"))
    )
    (comp (ref "C28")
      (value "CAPACITOR_0603_25V_1UF")
      (footprint "eagle-import:0603-CAP")
      (fields
        (field (name "CAPACITANCE") "1µF")
        (field (name "MANUFACTURER") "Samsung Electro-Mechanics")
        (field (name "MPN") "CL10B105KA8NNNC")
        (field (name "TOLERANCE") "10%")
        (field (name "VOLTAGE") "25V")
      )
      (libsource (lib "eagle-import") (part "CAPACITOR_?_060325V_1UF"))
    )
    (comp (ref "C29")
      (value "CAPACITOR_0603_35V_0.1UF")
      (footprint "eagle-import:0603-CAP")
      (fields
        (field (name "CAPACITANCE") "0.1µF")
        (field (name "MANUFACTURER") "Taiyo Yuden")
        (field (name "MPN") "GMK107B7104KAHT")
        (field (name "TOLERANCE") "10%")
        (field (name "VOLTAGE") "35V")
      )
      (libsource (lib "eagle-import") (part "CAPACITOR_?_060335V_0.1UF"))
    )
    (comp (ref "D2")
      (value "LED_0603_WHITE")
      (footprint "eagle-import:0603-LED")
      (fields
        (field (name "COLOR") "White")
        (field (name "MANUFACTURER") "Bivar Inc.")
        (field (name "MPN") "SM0603UWC")
      )
      (libsource (lib "eagle-import") (part "LED_?_0603WHITE"))
    )
    (comp (ref "D3")
      (value "LED_0603_GREEN")
      (footprint "eagle-import:0603-LED")
      (fields
        (field (name "COLOR") "Green")
        (field (name "MANUFACTURER") "Kingbright")
        (field (name "MPN") "APT1608ZGCK")
      )
      (libsource (lib "eagle-import") (part "LED_?_0603GREEN"))
    )
    (comp (ref "D5")
      (value "LED_0603_BLUE")
      (footprint "eagle-import:0603-LED")
      (fields
        (field (name "COLOR") "Blue")
        (field (name "MANUFACTURER") "Kingbright")
        (field (name "MPN") "APT1608VBC/D")
      )
      (libsource (lib "eagle-import") (part "LED_?_0603BLUE"))
    )
    (comp (ref "D6")
      (value "LED_0603_RED")
      (footprint "eagle-import:0603-LED")
      (fields
        (field (name "COLOR") "Red")
        (field (name "MANUFACTURER") "Kingbright")
        (field (name "MPN") "APT1608SECK/J3-PRV")
      )
      (libsource (lib "eagle-import") (part "LED_?_0603RED"))
    )
    (comp (ref "L4")
      (value "INDUCTOR_74451133_3.6UH")
      (footprint "eagle-import:74451133")
      (fields
        (field (name "INDUCTANCE") "3.6uH")
        (field (name "MANUFACTURER") "Pulse Electronics Power")
        (field (name "MPN") "PA4334.362NLT")
        (field (name "TOLERANCE") "20%")
      )
      (libsource (lib "eagle-import") (part "INDUCTOR_?_744511333.6UH"))
    )
    (comp (ref "L5")
      (value "INDUCTOR_WELMHI_56UH")
      (footprint "eagle-import:WE-LMHI")
      (fields
        (field (name "INDUCTANCE") "56µH")
        (field (name "MANUFACTURER") "Wurth Elektronik")
        (field (name "MPN") "74437349560")
        (field (name "TOLERANCE") "20%")
      )
      (libsource (lib "eagle-import") (part "INDUCTOR_?_WELMHI56UH"))
    )
    (comp (ref "R28")
      (value "RESISTOR_0603_1K")
      (footprint "eagle-import:0603-RES")
      (fields
        (field (name "MANUFACTURER") "Yageo")
        (field (name "MPN") "RC0603FR-071KL")
        (field (name "POWER") "0.1W")
        (field (name "RESISTANCE") "1k")
      )
      (libsource (lib "eagle-import") (part "RESISTOR_?_06031K"))
    )
    (comp (ref "R29")
      (value "RESISTOR_0603_1K")
      (footprint "eagle-import:0603-RES")
      (fields
        (field (name "MANUFACTURER") "Yageo")
        (field (name "MPN") "RC0603FR-071KL")
        (field (name "POWER") "0.1W")
        (field (name "RESISTANCE") "1k")
      )
      (libsource (lib "eagle-import") (part "RESISTOR_?_06031K"))
    )
    (comp (ref "R30")
      (value "RESISTOR_0603_1K")
      (footprint "eagle-import:0603-RES")
      (fields
        (field (name "MANUFACTURER") "Yageo")
        (field (name "MPN") "RC0603FR-071KL")
        (field (name "POWER") "0.1W")
        (field (name "RESISTANCE") "1k")
      )
      (libsource (lib "eagle-import") (part "RESISTOR_?_06031K"))
    )
    (comp (ref "R31")
      (value "RESISTOR_0603_1.62")
      (footprint "eagle-import:0603-RES")
      (fields
        (field (name "MANUFACTURER") "TE Conductivity Passive Product")
        (field (name "MPN") "CPF0603B1R62E1")
        (field (name "POWER") "0.1W")
        (field (name "RESISTANCE") "1.62")
      )
      (libsource (lib "eagle-import") (part "RESISTOR_?_06031.62"))
    )
    (comp (ref "R32")
      (value "RESISTOR_0603_1K")
      (footprint "eagle-import:0603-RES")
      (fields
        (field (name "MANUFACTURER") "Yageo")
        (field (name "MPN") "RC0603FR-071KL")
        (field (name "POWER") "0.1W")
        (field (name "RESISTANCE") "1k")
      )
      (libsource (lib "eagle-import") (part "RESISTOR_?_06031K"))
    )
    (comp (ref "R33")
      (value "RESISTOR_0603_DNP")
      (footprint "eagle-import:0603-RES")
      (fields (field (name "RESISTANCE") "DNP"))
      (libsource (lib "eagle-import") (part "RESISTOR_?_0603DNP"))
    )
    (comp (ref "R34")
      (value "RESISTOR_0603_1K")
      (footprint "eagle-import:0603-RES")
      (fields
        (field (name "MANUFACTURER") "Yageo")
        (field (name "MPN") "RC0603FR-071KL")
        (field (name "POWER") "0.1W")
        (field (name "RESISTANCE") "1k")
      )
      (libsource (lib "eagle-import") (part "RESISTOR_?_06031K"))
    )
    (comp (ref "R44")
      (value "RESISTOR_0805_1M")
      (footprint "eagle-import:0805-RES")
      (fields
        (field (name "MANUFACTURER") "Panasonic Electronic Components")
        (field (name "MPN") "ERJ-PB6B1004V")
        (field (name "POWER") "0.25W")
        (field (name "RESISTANCE") "1M")
      )
      (libsource (lib "eagle-import") (part "RESISTOR_?_08051M"))
    )
    (comp (ref "R46")
      (value "RESISTOR_0805_523K")
      (footprint "eagle-import:0805-RES")
      (fields
        (field (name "MANUFACTURER") "Panasonic Electronic Components")
        (field (name "MPN") "ERJ-PB6B5233V")
        (field (name "POWER") "0.25W")
        (field (name "RESISTANCE") "523k")
      )
      (libsource (lib "eagle-import") (part "RESISTOR_?_0805523K"))
    )
    (comp (ref "R51")
      (value "RESISTOR_0603_154K")
      (footprint "eagle-import:0603-RES")
      (fields
        (field (name "MANUFACTURER") "Panasonic Electronic Components")
        (field (name "MPN") "ERA-3AEB1543V")
        (field (name "POWER") "0.1W")
        (field (name "RESISTANCE") "154k")
      )
      (libsource (lib "eagle-import") (part "RESISTOR_?_0603154K"))
    )
    (comp (ref "U1")
      (value "LTC6994_1")
      (footprint "eagle-import:SOT-23-6")
      (fields (field (name "MANUFACTURER") "Analog Electronics") (field (name "MPN") "LTC6994CS6-1#TRMPBF"))
      (libsource (lib "eagle-import") (part "LTC6994_1"))
    )
    (comp (ref "U10")
      (value "DCM4623TD2J13D0T70")
      (footprint "eagle-import:DCM4623")
      (fields (field (name "MANUFACTURER") "Vicor"))
      (libsource (lib "eagle-import") (part "DCM4623TD2J13D0T70"))
    )
    (comp (ref "U11")
      (value "RELAY_SOLIDSTATE_NC_AG")
      (footprint "eagle-import:DIP-4_AIRGAP")
      (fields (field (name "MPN") "AQY414EHA") (field (name "MANUFACTURER") "Panasonic Industrial Devices"))
      (libsource (lib "eagle-import") (part "RELAY_SOLIDSTATE_NC_?AG"))
    )
    (comp (ref "XF1")
      (value "FUSE_HOLDER_MINIBLADEPTH")
      (footprint "eagle-import:3568")
      (fields (field (name "MANUFACTURER") "Keystone") (field (name "MPN") "3568"))
      (libsource (lib "eagle-import") (part "FUSE_HOLDER_PTHMINIBLADE"))
    )
  )
  (nets
    (net (code "1") (name "+12V") (class "Default")
      (node (ref "C6") (pin "1") (pinfunction "1_1") (pintype "passive"))
      (node (ref "C8") (pin "1") (pinfunction "1_1") (pintype "passive"))
      (node (ref "J3") (pin "1") (pinfunction "1_1") (pintype "passive"))
      (node (ref "R35") (pin "2") (pinfunction "2_2") (pintype "passive"))
      (node (ref "TP1") (pin "1") (pinfunction "P$1_1") (pintype "passive"))
      (node (ref "U2") (pin "3") (pinfunction "IN_3") (pintype "power_in"))
    )
    (net (code "2") (name "DCDC+") (class "Default")
      (node (ref "J5") (pin "1") (pinfunction "1_1") (pintype "passive"))
      (node (ref "J5") (pin "3") (pinfunction "3_3") (pintype "passive"))
      (node (ref "R30") (pin "2") (pinfunction "2_2") (pintype "passive"))
      (node (ref "TP9") (pin "1") (pinfunction "P$1_1") (pintype "passive"))
      (node (ref "XF1") (pin "3") (pinfunction "2_3") (pintype "passive"))
      (node (ref "XF1") (pin "4") (pinfunction "2_4") (pintype "passive"))
    )
    (net (code "3") (name "DCDC-") (class "Default")
      (node (ref "C26") (pin "-") (pinfunction "MINUS_-") (pintype "passive"))
      (node (ref "C27") (pin "1") (pinfunction "1_1") (pintype "passive"))
      (node (ref "C28") (pin "1") (pinfunction "1_1") (pintype "passive"))
      (node (ref "C29") (pin "1") (pinfunction "1_1") (pintype "passive"))
      (node (ref "D5") (pin "1") (pinfunction "C_1") (pintype "passive"))
      (node (ref "J5") (pin "2") (pinfunction "2_2") (pintype "passive"))
      (node (ref "J5") (pin "4") (pinfunction "4_4") (pintype "passive"))
      (node (ref "TP10") (pin "1") (pinfunction "P$1_1") (pintype "passive"))
      (node (ref "U10") (pin "7") (pinfunction "-OUT_7") (pintype "power_in"))
      (node (ref "U10") (pin "9") (pinfunction "-OUT_9") (pintype "power_in"))
    )
    (net (code "4") (name "ENABLE") (class "Default")
      (node (ref "U10") (pin "3") (pinfunction "EN_3") (pintype "input"))
      (node (ref "U11") (pin "4") (pinfunction "CONTACT2_4") (pintype "bidirectional"))
    )
    (net (code "5") (name "GND") (class "Default")
      (node (ref "C10") (pin "2") (pinfunction "2_2") (pintype "passive"))
      (node (ref "C11") (pin "2") (pinfunction "2_2") (pintype "passive"))
      (node (ref "C41") (pin "2") (pinfunction "2_2") (pintype "passive"))
      (node (ref "C42") (pin "2") (pinfunction "2_2") (pintype "passive"))
      (node (ref "C43") (pin "2") (pinfunction "2_2") (pintype "passive"))
      (node (ref "C44") (pin "2") (pinfunction "2_2") (pintype "passive"))
      (node (ref "C5") (pin "2") (pinfunction "2_2") (pintype "passive"))
      (node (ref "C6") (pin "2") (pinfunction "2_2") (pintype "passive"))
      (node (ref "C7") (pin "2") (pinfunction "2_2") (pintype "passive"))
      (node (ref "C8") (pin "2") (pinfunction "2_2") (pintype "passive"))
      (node (ref "C9") (pin "2") (pinfunction "2_2") (pintype "passive"))
      (node (ref "D1") (pin "1") (pinfunction "A_1") (pintype "passive"))
      (node (ref "D11") (pin "1") (pinfunction "C_1") (pintype "passive"))
      (node (ref "D12") (pin "1") (pinfunction "C_1") (pintype "passive"))
      (node (ref "D2") (pin "1") (pinfunction "C_1") (pintype "passive"))
      (node (ref "D3") (pin "1") (pinfunction "C_1") (pintype "passive"))
      (node (ref "D4") (pin "1") (pinfunction "C_1") (pintype "passive"))
      (node (ref "D7") (pin "A") (pinfunction "A_A") (pintype "passive"))
      (node (ref "D9") (pin "1") (pinfunction "C_1") (pintype "passive"))
      (node (ref "J3") (pin "4") (pinfunction "4_4") (pintype "passive"))
      (node (ref "K4") (pin "3") (pinfunction "COIL-_3") (pintype "bidirectional"))
      (node (ref "Q2") (pin "2") (pinfunction "S_2") (pintype "passive"))
      (node (ref "R38") (pin "1") (pinfunction "1_1") (pintype "passive"))
      (node (ref "R46") (pin "1") (pinfunction "1_1") (pintype "passive"))
      (node (ref "R51") (pin "1") (pinfunction "1_1") (pintype "passive"))
      (node (ref "TP3") (pin "1") (pinfunction "P$1_1") (pintype "passive"))
      (node (ref "U$1") (pin "2") (pinfunction "CONTROL-_2") (pintype "passive"))
      (node (ref "U1") (pin "2") (pinfunction "GND_2") (pintype "power_in"))
      (node (ref "U11") (pin "2") (pinfunction "CONTROL-_2") (pintype "passive"))
      (node (ref "U15") (pin "3") (pinfunction "GND_3") (pintype "power_in"))
      (node (ref "U18") (pin "5") (pinfunction "GND2_5") (pintype "power_in"))
      (node (ref "U19") (pin "5") (pinfunction "GND2_5") (pintype "power_in"))
      (node (ref "U2") (pin "1") (pinfunction "GND_1") (pintype "power_in"))
    )
    (net (code "6") (name "IP+") (class "Default")
      (node (ref "J3") (pin "5") (pinfunction "5_5") (pintype "passive"))
      (node (ref "TP5") (pin "1") (pinfunction "P$1_1") (pintype "passive"))
      (node (ref "U19") (pin "7") (pinfunction "OUTP_7") (pintype "output"))
    )
    (net (code "7") (name "IP-") (class "Default")
      (node (ref "J3") (pin "6") (pinfunction "6_6") (pintype "passive"))
      (node (ref "TP6") (pin "1") (pinfunction "P$1_1") (pintype "passive"))
      (node (ref "U19") (pin "6") (pinfunction "OUTN_6") (pintype "output"))
    )
    (net (code "8") (name "IT+") (class "Default")
      (node (ref "J3") (pin "7") (pinfunction "7_7") (pintype "passive"))
      (node (ref "TP7") (pin "1") (pinfunction "P$1_1") (pintype "passive"))
      (node (ref "U18") (pin "7") (pinfunction "OUTP_7") (pintype "output"))
    )
    (net (code "9") (name "IT-") (class "Default")
      (node (ref "J3") (pin "8") (pinfunction "8_8") (pintype "passive"))
      (node (ref "TP8") (pin "1") (pinfunction "P$1_1") (pintype "passive"))
      (node (ref "U18") (pin "6") (pinfunction "OUTN_6") (pintype "output"))
    )
    (net (code "10") (name "LED+") (class "Default")
      (node (ref "J1") (pin "3") (pinfunction "3_3") (pintype "passive"))
      (node (ref "R63") (pin "2") (pinfunction "2_2") (pintype "passive"))
    )
    (net (code "11") (name "Net-(C26-PLUS)") (class "Default")
      (node (ref "C26") (pin "+") (pinfunction "PLUS_+") (pintype "passive"))
      (node (ref "C27") (pin "2") (pinfunction "2_2") (pintype "passive"))
      (node (ref "C28") (pin "2") (pinfunction "2_2") (pintype "passive"))
      (node (ref "C29") (pin "2") (pinfunction "2_2") (pintype "passive"))
      (node (ref "U10") (pin "6") (pinfunction "+OUT_6") (pintype "power_in"))
      (node (ref "U10") (pin "8") (pinfunction "+OUT_8") (pintype "power_in"))
      (node (ref "XF1") (pin "1") (pinfunction "1_1") (pintype "passive"))
      (node (ref "XF1") (pin "2") (pinfunction "1_2") (pintype "passive"))
    )
    (net (code "12") (name "Net-(C35-Pad2)") (class "Default")
      (node (ref "C35") (pin "2") (pinfunction "2_2") (pintype "passive"))
      (node (ref "R47") (pin "2") (pinfunction "2_2") (pintype "passive"))
    )
    (net (code "13") (name "Net-(D1-C)") (class "Default")
      (node (ref "D1") (pin "3") (pinfunction "C_3") (pintype "passive"))
      (node (ref "R37") (pin "1") (pinfunction "1_1") (pintype "passive"))
      (node (ref "R38") (pin "2") (pinfunction "2_2") (pintype "passive"))
      (node (ref "R52") (pin "2") (pinfunction "2_2") (pintype "passive"))
      (node (ref "U15") (pin "4") (pinfunction "~{IN}_4") (pintype "output"))
    )
    (net (code "14") (name "Net-(D2-A)") (class "Default")
      (node (ref "D2") (pin "2") (pinfunction "A_2") (pintype "passive"))
      (node (ref "R28") (pin "1") (pinfunction "1_1") (pintype "passive"))
    )
    (net (code "15") (name "Net-(D3-A)") (class "Default")
      (node (ref "D3") (pin "2") (pinfunction "A_2") (pintype "passive"))
      (node (ref "R29") (pin "1") (pinfunction "1_1") (pintype "passive"))
    )
    (net (code "16") (name "Net-(D4-A)") (class "Default")
      (node (ref "D4") (pin "2") (pinfunction "A_2") (pintype "passive"))
      (node (ref "R52") (pin "1") (pinfunction "1_1") (pintype "passive"))
    )
    (net (code "17") (name "Net-(D5-A)") (class "Default")
      (node (ref "D5") (pin "2") (pinfunction "A_2") (pintype "passive"))
      (node (ref "R30") (pin "1") (pinfunction "1_1") (pintype "passive"))
    )
    (net (code "18") (name "Net-(D6-A)") (class "Default")
      (node (ref "D6") (pin "2") (pinfunction "A_2") (pintype "passive"))
      (node (ref "R32") (pin "2") (pinfunction "2_2") (pintype "passive"))
    )
    (net (code "19") (name "Net-(D9-A)") (class "Default")
      (node (ref "D9") (pin "2") (pinfunction "A_2") (pintype "passive"))
      (node (ref "R35") (pin "1") (pinfunction "1_1") (pintype "passive"))
    )
    (net (code "20") (name "Net-(D11-A)") (class "Default")
      (node (ref "D11") (pin "2") (pinfunction "A_2") (pintype "passive"))
      (node (ref "R53") (pin "2") (pinfunction "2_2") (pintype "passive"))
    )
    (net (code "21") (name "Net-(D12-A)") (class "Default")
      (node (ref "D12") (pin "2") (pinfunction "A_2") (pintype "passive"))
      (node (ref "R54") (pin "1") (pinfunction "1_1") (pintype "passive"))
    )
    (net (code "22") (name "Net-(D13-A)") (class "Default")
      (node (ref "D13") (pin "2") (pinfunction "A_2") (pintype "passive"))
      (node (ref "R55") (pin "1") (pinfunction "1_1") (pintype "passive"))
    )
    (net (code "23") (name "Net-(K4-CONTACT2)") (class "Default")
      (node (ref "K4") (pin "4") (pinfunction "CONTACT2_4") (pintype "bidirectional"))
      (node (ref "R18") (pin "2") (pinfunction "2_2") (pintype "passive"))
    )
    (net (code "24") (name "Net-(K5-COIL-)") (class "Default")
      (node (ref "D8") (pin "A") (pinfunction "A_A") (pintype "passive"))
      (node (ref "K5") (pin "3") (pinfunction "COIL-_3") (pintype "bidirectional"))
      (node (ref "Q2") (pin "3") (pinfunction "D_3") (pintype "passive"))
    )
    (net (code "25") (name "Net-(K5-CONTACT2)") (class "Default")
      (node (ref "K5") (pin "4") (pinfunction "CONTACT2_4") (pintype "bidirectional"))
      (node (ref "R19") (pin "1") (pinfunction "1_1") (pintype "passive"))
    )
    (net (code "26") (name "Net-(L4-Pad2)") (class "Default")
      (node (ref "L4") (pin "2") (pinfunction "2_2") (pintype "passive"))
      (node (ref "R31") (pin "1") (pinfunction "1_1") (pintype "passive"))
    )
    (net (code "27") (name "Net-(Q2-G)") (class "Default")
      (node (ref "Q2") (pin "1") (pinfunction "G_1") (pintype "passive"))
      (node (ref "R37") (pin "2") (pinfunction "2_2") (pintype "passive"))
    )
    (net (code "28") (name "Net-(R1-Pad1)") (class "Default")
      (node (ref "R1") (pin "1") (pinfunction "1_1") (pintype "passive"))
      (node (ref "R2") (pin "2") (pinfunction "2_2") (pintype "passive"))
    )
    (net (code "29") (name "Net-(R2-Pad1)") (class "Default")
      (node (ref "R2") (pin "1") (pinfunction "1_1") (pintype "passive"))
      (node (ref "R50") (pin "1") (pinfunction "1_1") (pintype "passive"))
      (node (ref "R6") (pin "2") (pinfunction "2_2") (pintype "passive"))
      (node (ref "R7") (pin "2") (pinfunction "2_2") (pintype "passive"))
    )
    (net (code "30") (name "Net-(R10-Pad1)") (class "Default")
      (node (ref "R10") (pin "1") (pinfunction "1_1") (pintype "passive"))
      (node (ref "R11") (pin "2") (pinfunction "2_2") (pintype "passive"))
    )
    (net (code "31") (name "Net-(R11-Pad1)") (class "Default")
      (node (ref "R11") (pin "1") (pinfunction "1_1") (pintype "passive"))
      (node (ref "R49") (pin "1") (pinfunction "1_1") (pintype "passive"))
      (node (ref "R8") (pin "2") (pinfunction "2_2") (pintype "passive"))
      (node (ref "R9") (pin "2") (pinfunction "2_2") (pintype "passive"))
    )
    (net (code "32") (name "Net-(U$1-CONTACT1)") (class "Default")
      (node (ref "R27") (pin "2") (pinfunction "2_2") (pintype "passive"))
      (node (ref "U$1") (pin "3") (pinfunction "CONTACT1_3") (pintype "bidirectional"))
    )
    (net (code "33") (name "Net-(U$1-CONTROL+)") (class "Default")
      (node (ref "R36") (pin "1") (pinfunction "1_1") (pintype "passive"))
      (node (ref "U$1") (pin "1") (pinfunction "CONTROL+_1") (pintype "passive"))
    )
    (net (code "34") (name "Net-(U1-DIV)") (class "Default")
      (node (ref "R44") (pin "1") (pinfunction "1_1") (pintype "passive"))
      (node (ref "R46") (pin "2") (pinfunction "2_2") (pintype "passive"))
      (node (ref "U1") (pin "6") (pinfunction "DIV_6") (pintype "bidirectional"))
    )
    (net (code "35") (name "Net-(U1-OUT)") (class "Default")
      (node (ref "R28") (pin "2") (pinfunction "2_2") (pintype "passive"))
      (node (ref "R34") (pin "1") (pinfunction "1_1") (pintype "passive"))
      (node (ref "U1") (pin "4") (pinfunction "OUT_4") (pintype "bidirectional"))
    )
    (net (code "36") (name "Net-(U1-SET)") (class "Default")
      (node (ref "C11") (pin "1") (pinfunction "1_1") (pintype "passive"))
      (node (ref "R51") (pin "2") (pinfunction "2_2") (pintype "passive"))
      (node (ref "U1") (pin "3") (pinfunction "SET_3") (pintype "bidirectional"))
    )
    (net (code "37") (name "Net-(U10-+IN)") (class "Default")
      (node (ref "C1") (pin "1") (pinfunction "1_1") (pintype "passive"))
      (node (ref "C24") (pin "1") (pinfunction "1_1") (pintype "passive"))
      (node (ref "C25") (pin "1") (pinfunction "1_1") (pintype "passive"))
      (node (ref "L4") (pin "1") (pinfunction "1_1") (pintype "passive"))
      (node (ref "L5") (pin "1") (pinfunction "1_1") (pintype "passive"))
      (node (ref "U10") (pin "1") (pinfunction "+IN_1") (pintype "power_in"))
    )
    (net (code "38") (name "Net-(U10-FLT)") (class "Default")
      (node (ref "R32") (pin "1") (pinfunction "1_1") (pintype "passive"))
      (node (ref "U10") (pin "4") (pinfunction "FLT_4") (pintype "output"))
    )
    (net (code "39") (name "Net-(U10-TR)") (class "Default")
      (node (ref "R33") (pin "1") (pinfunction "1_1") (pintype "passive"))
      (node (ref "U10") (pin "2") (pinfunction "TR_2") (pintype "output"))
    )
    (net (code "40") (name "Net-(U11-CONTROL+)") (class "Default")
      (node (ref "R34") (pin "2") (pinfunction "2_2") (pintype "passive"))
      (node (ref "U11") (pin "1") (pinfunction "CONTROL+_1") (pintype "passive"))
    )
    (net (code "41") (name "Net-(U16-ISET)") (class "Default")
      (node (ref "R48") (pin "2") (pinfunction "2_2") (pintype "passive"))
      (node (ref "U16") (pin "11") (pinfunction "ISET_11") (pintype "bidirectional"))
    )
    (net (code "42") (name "Net-(U16-OVLO)") (class "Default")
      (node (ref "R3") (pin "2") (pinfunction "2_2") (pintype "passive"))
      (node (ref "R4") (pin "1") (pinfunction "1_1") (pintype "passive"))
      (node (ref "U16") (pin "12") (pinfunction "OVLO_12") (pintype "input"))
    )
    (net (code "43") (name "Net-(U16-RUN)") (class "Default")
      (node (ref "R4") (pin "2") (pinfunction "2_2") (pintype "passive"))
      (node (ref "R5") (pin "1") (pinfunction "1_1") (pintype "passive"))
      (node (ref "U16") (pin "14") (pinfunction "RUN_14") (pintype "input"))
    )
    (net (code "44") (name "Net-(U16-SS)") (class "Default")
      (node (ref "U16") (pin "10") (pinfunction "SS_10") (pintype "input"))
      (node (ref "U16") (pin "7") (pinfunction "VPRG1_7") (pintype "input"))
    )
    (net (code "45") (name "Net-(U16-SW)") (class "Default")
      (node (ref "L6") (pin "1") (pinfunction "1_1") (pintype "passive"))
      (node (ref "U16") (pin "1") (pinfunction "SW_1") (pintype "power_in"))
    )
    (net (code "46") (name "Net-(U16-VDD)") (class "Default")
      (node (ref "C32") (pin "1") (pinfunction "1_1") (pintype "passive"))
      (node (ref "C33") (pin "1") (pinfunction "1_1") (pintype "passive"))
      (node (ref "C35") (pin "1") (pinfunction "1_1") (pintype "passive"))
      (node (ref "C4") (pin "1") (pinfunction "1_1") (pintype "passive"))
      (node (ref "D10") (pin "C") (pinfunction "C_C") (pintype "passive"))
      (node (ref "R5") (pin "2") (pinfunction "2_2") (pintype "passive"))
      (node (ref "U16") (pin "3") (pinfunction "VDD_3") (pintype "power_in"))
    )
    (net (code "47") (name "Net-(U17-ADJ)") (class "Default")
      (node (ref "R43") (pin "2") (pinfunction "2_2") (pintype "passive"))
      (node (ref "R45") (pin "1") (pinfunction "1_1") (pintype "passive"))
      (node (ref "U17") (pin "3") (pinfunction "ADJ_3") (pintype "input"))
    )
    (net (code "48") (name "Net-(U17-IN)") (class "Default")
      (node (ref "C2") (pin "1") (pinfunction "1_1") (pintype "passive"))
      (node (ref "C30") (pin "1") (pinfunction "1_1") (pintype "passive"))
      (node (ref "D14") (pin "C") (pinfunction "C_C") (pintype "passive"))
      (node (ref "R26") (pin "2") (pinfunction "2_2") (pintype "passive"))
      (node (ref "U17") (pin "1") (pinfunction "IN_1") (pintype "power_in"))
    )
    (net (code "49") (name "Net-(U17-OUT)") (class "Default")
      (node (ref "C3") (pin "1") (pinfunction "1_1") (pintype "passive"))
      (node (ref "C31") (pin "1") (pinfunction "1_1") (pintype "passive"))
      (node (ref "D10") (pin "A") (pinfunction "A_A") (pintype "passive"))
      (node (ref "D14") (pin "A") (pinfunction "A_A") (pintype "passive"))
      (node (ref "R45") (pin "2") (pinfunction "2_2") (pintype "passive"))
      (node (ref "R47") (pin "1") (pinfunction "1_1") (pintype "passive"))
      (node (ref "U17") (pin "2") (pinfunction "OUT_2") (pintype "power_in"))
    )
    (net (code "50") (name "Net-(U18-IN)") (class "Default")
      (node (ref "C49") (pin "1") (pinfunction "1_1") (pintype "passive"))
      (node (ref "R50") (pin "2") (pinfunction "2_2") (pintype "passive"))
      (node (ref "U18") (pin "2") (pinfunction "IN_2") (pintype "input"))
    )
    (net (code "51") (name "Net-(U18-VCAP)") (class "Default")
      (node (ref "C38") (pin "1") (pinfunction "1_1") (pintype "passive"))
      (node (ref "U18") (pin "1") (pinfunction "VCAP_1") (pintype "passive"))
    )
    (net (code "52") (name "Net-(U19-IN)") (class "Default")
      (node (ref "C48") (pin "1") (pinfunction "1_1") (pintype "passive"))
      (node (ref "R49") (pin "2") (pinfunction "2_2") (pintype "passive"))
      (node (ref "U19") (pin "2") (pinfunction "IN_2") (pintype "input"))
    )
    (net (code "53") (name "Net-(U19-VCAP)") (class "Default")
      (node (ref "C45") (pin "1") (pinfunction "1_1") (pintype "passive"))
      (node (ref "U19") (pin "1") (pinfunction "VCAP_1") (pintype "passive"))
    )
    (net (code "54") (name "PACK+") (class "Default")
      (node (ref "J2") (pin "5") (pinfunction "5_5") (pintype "passive"))
      (node (ref "K5") (pin "1") (pinfunction "CONTACT1_1") (pintype "bidirectional"))
      (node (ref "TP12") (pin "1") (pinfunction "P$1_1") (pintype "passive"))
      (node (ref "U$1") (pin "4") (pinfunction "CONTACT2_4") (pintype "bidirectional"))
    )
    (net (code "55") (name "PACK+FUSED") (class "Default")
      (node (ref "R10") (pin "2") (pinfunction "2_2") (pintype "passive"))
      (node (ref "R27") (pin "1") (pinfunction "1_1") (pintype "passive"))
      (node (ref "TP13") (pin "1") (pinfunction "P$1_1") (pintype "passive"))
    )
    (net (code "56") (name "PRECHARGE_OK") (class "Default")
      (node (ref "J3") (pin "3") (pinfunction "3_3") (pintype "passive"))
      (node (ref "R29") (pin "2") (pinfunction "2_2") (pintype "passive"))
      (node (ref "TP4") (pin "1") (pinfunction "P$1_1") (pintype "passive"))
      (node (ref "U1") (pin "1") (pinfunction "IN_1") (pintype "bidirectional"))
      (node (ref "U15") (pin "2") (pinfunction "IN_2") (pintype "input"))
    )
    (net (code "57") (name "SHDN") (class "Default")
      (node (ref "D7") (pin "C") (pinfunction "C_C") (pintype "passive"))
      (node (ref "D8") (pin "C") (pinfunction "C_C") (pintype "passive"))
      (node (ref "J3") (pin "2") (pinfunction "2_2") (pintype "passive"))
      (node (ref "K4") (pin "2") (pinfunction "COIL+_2") (pintype "bidirectional"))
      (node (ref "K5") (pin "2") (pinfunction "COIL+_2") (pintype "bidirectional"))
      (node (ref "R36") (pin "2") (pinfunction "2_2") (pintype "passive"))
      (node (ref "R54") (pin "2") (pinfunction "2_2") (pintype "passive"))
      (node (ref "TP11") (pin "1") (pinfunction "P$1_1") (pintype "passive"))
    )
    (net (code "58") (name "TS+5V") (class "Default")
      (node (ref "C34") (pin "1") (pinfunction "1_1") (pintype "passive"))
      (node (ref "C36") (pin "1") (pinfunction "1_1") (pintype "passive"))
      (node (ref "C37") (pin "1") (pinfunction "1_1") (pintype "passive"))
      (node (ref "C39") (pin "1") (pinfunction "1_1") (pintype "passive"))
      (node (ref "C40") (pin "1") (pinfunction "1_1") (pintype "passive"))
      (node (ref "C46") (pin "1") (pinfunction "1_1") (pintype "passive"))
      (node (ref "C47") (pin "1") (pinfunction "1_1") (pintype "passive"))
      (node (ref "L6") (pin "2") (pinfunction "2_2") (pintype "passive"))
      (node (ref "R55") (pin "2") (pinfunction "2_2") (pintype "passive"))
      (node (ref "R63") (pin "1") (pinfunction "1_1") (pintype "passive"))
      (node (ref "TP20") (pin "1") (pinfunction "P$1_1") (pintype "passive"))
      (node (ref "U16") (pin "9") (pinfunction "VFB_9") (pintype "input"))
      (node (ref "U18") (pin "3") (pinfunction "VDD1_3") (pintype "power_in"))
      (node (ref "U19") (pin "3") (pinfunction "VDD1_3") (pintype "power_in"))
    )
    (net (code "59") (name "TS+FUSED") (class "Default")
      (node (ref "F6") (pin "2") (pinfunction "2_2") (pintype "passive"))
      (node (ref "J2") (pin "4") (pinfunction "4_4") (pintype "passive"))
      (node (ref "L5") (pin "2") (pinfunction "2_2") (pintype "passive"))
      (node (ref "R1") (pin "2") (pinfunction "2_2") (pintype "passive"))
      (node (ref "R26") (pin "1") (pinfunction "1_1") (pintype "passive"))
      (node (ref "R31") (pin "2") (pinfunction "2_2") (pintype "passive"))
    )
    (net (code "60") (name "TS+UNFUSED") (class "Default")
      (node (ref "F6") (pin "1") (pinfunction "1_1") (pintype "passive"))
      (node (ref "J2") (pin "1") (pinfunction "1_1") (pintype "passive"))
      (node (ref "J2") (pin "2") (pinfunction "2_2") (pintype "passive"))
      (node (ref "K4") (pin "1") (pinfunction "CONTACT1_1") (pintype "bidirectional"))
      (node (ref "R16") (pin "1") (pinfunction "1_1") (pintype "passive"))
      (node (ref "R19") (pin "2") (pinfunction "2_2") (pintype "passive"))
      (node (ref "TP14") (pin "1") (pinfunction "P$1_1") (pintype "passive"))
    )
    (net (code "61") (name "TS-FUSED") (class "Default")
      (node (ref "C1") (pin "2") (pinfunction "2_2") (pintype "passive"))
      (node (ref "C2") (pin "2") (pinfunction "2_2") (pintype "passive"))
      (node (ref "C24") (pin "2") (pinfunction "2_2") (pintype "passive"))
      (node (ref "C25") (pin "2") (pinfunction "2_2") (pintype "passive"))
      (node (ref "C3") (pin "2") (pinfunction "2_2") (pintype "passive"))
      (node (ref "C30") (pin "2") (pinfunction "2_2") (pintype "passive"))
      (node (ref "C31") (pin "2") (pinfunction "2_2") (pintype "passive"))
      (node (ref "C32") (pin "2") (pinfunction "2_2") (pintype "passive"))
      (node (ref "C33") (pin "2") (pinfunction "2_2") (pintype "passive"))
      (node (ref "C34") (pin "2") (pinfunction "2_2") (pintype "passive"))
      (node (ref "C36") (pin "2") (pinfunction "2_2") (pintype "passive"))
      (node (ref "C37") (pin "2") (pinfunction "2_2") (pintype "passive"))
      (node (ref "C38") (pin "2") (pinfunction "2_2") (pintype "passive"))
      (node (ref "C39") (pin "2") (pinfunction "2_2") (pintype "passive"))
      (node (ref "C4") (pin "2") (pinfunction "2_2") (pintype "passive"))
      (node (ref "C40") (pin "2") (pinfunction "2_2") (pintype "passive"))
      (node (ref "C45") (pin "2") (pinfunction "2_2") (pintype "passive"))
      (node (ref "C46") (pin "2") (pinfunction "2_2") (pintype "passive"))
      (node (ref "C47") (pin "2") (pinfunction "2_2") (pintype "passive"))
      (node (ref "C48") (pin "2") (pinfunction "2_2") (pintype "passive"))
      (node (ref "C49") (pin "2") (pinfunction "2_2") (pintype "passive"))
      (node (ref "D13") (pin "1") (pinfunction "C_1") (pintype "passive"))
      (node (ref "D6") (pin "1") (pinfunction "C_1") (pintype "passive"))
      (node (ref "F2") (pin "2") (pinfunction "2_2") (pintype "passive"))
      (node (ref "J1") (pin "1") (pinfunction "1_1") (pintype "passive"))
      (node (ref "J1") (pin "2") (pinfunction "2_2") (pintype "passive"))
      (node (ref "R3") (pin "1") (pinfunction "1_1") (pintype "passive"))
      (node (ref "R33") (pin "2") (pinfunction "2_2") (pintype "passive"))
      (node (ref "R43") (pin "1") (pinfunction "1_1") (pintype "passive"))
      (node (ref "R48") (pin "1") (pinfunction "1_1") (pintype "passive"))
      (node (ref "R6") (pin "1") (pinfunction "1_1") (pintype "passive"))
      (node (ref "R7") (pin "1") (pinfunction "1_1") (pintype "passive"))
      (node (ref "R8") (pin "1") (pinfunction "1_1") (pintype "passive"))
      (node (ref "R9") (pin "1") (pinfunction "1_1") (pintype "passive"))
      (node (ref "TP16") (pin "1") (pinfunction "P$1_1") (pintype "passive"))
      (node (ref "U10") (pin "5") (pinfunction "-IN_5") (pintype "power_in"))
      (node (ref "U11") (pin "3") (pinfunction "CONTACT1_3") (pintype "bidirectional"))
      (node (ref "U16") (pin "16") (pinfunction "GND_16") (pintype "power_in"))
      (node (ref "U16") (pin "6") (pinfunction "VPRG2_6") (pintype "input"))
      (node (ref "U16") (pin "8") (pinfunction "GND_8") (pintype "power_in"))
      (node (ref "U18") (pin "4") (pinfunction "GND1_4") (pintype "power_in"))
      (node (ref "U19") (pin "4") (pinfunction "GND1_4") (pintype "power_in"))
    )
    (net (code "62") (name "TS-UNFUSED") (class "Default")
      (node (ref "F2") (pin "1") (pinfunction "1_1") (pintype "passive"))
      (node (ref "J1") (pin "5") (pinfunction "5_5") (pintype "passive"))
      (node (ref "R17") (pin "1") (pinfunction "1_1") (pintype "passive"))
      (node (ref "R18") (pin "1") (pinfunction "1_1") (pintype "passive"))
      (node (ref "TP15") (pin "1") (pinfunction "P$1_1") (pintype "passive"))
    )
    (net (code "63") (name "TSMP+") (class "Default")
      (node (ref "J2") (pin "3") (pinfunction "3_3") (pintype "passive"))
      (node (ref "R16") (pin "2") (pinfunction "2_2") (pintype "passive"))
      (node (ref "TP18") (pin "1") (pinfunction "P$1_1") (pintype "passive"))
    )
    (net (code "64") (name "TSMP-") (class "Default")
      (node (ref "J1") (pin "4") (pinfunction "4_4") (pintype "passive"))
      (node (ref "R17") (pin "2") (pinfunction "2_2") (pintype "passive"))
      (node (ref "TP19") (pin "1") (pinfunction "P$1_1") (pintype "passive"))
    )
    (net (code "65") (name "VDD") (class "Default")
      (node (ref "C10") (pin "1") (pinfunction "1_1") (pintype "passive"))
      (node (ref "C41") (pin "1") (pinfunction "1_1") (pintype "passive"))
      (node (ref "C42") (pin "1") (pinfunction "1_1") (pintype "passive"))
      (node (ref "C43") (pin "1") (pinfunction "1_1") (pintype "passive"))
      (node (ref "C44") (pin "1") (pinfunction "1_1") (pintype "passive"))
      (node (ref "C5") (pin "1") (pinfunction "1_1") (pintype "passive"))
      (node (ref "C7") (pin "1") (pinfunction "1_1") (pintype "passive"))
      (node (ref "C9") (pin "1") (pinfunction "1_1") (pintype "passive"))
      (node (ref "R44") (pin "2") (pinfunction "2_2") (pintype "passive"))
      (node (ref "R53") (pin "1") (pinfunction "1_1") (pintype "passive"))
      (node (ref "TP2") (pin "1") (pinfunction "P$1_1") (pintype "passive"))
      (node (ref "U1") (pin "5") (pinfunction "V+_5") (pintype "power_in"))
      (node (ref "U15") (pin "5") (pinfunction "VDD_5") (pintype "power_in"))
      (node (ref "U18") (pin "8") (pinfunction "VDD2_8") (pintype "power_in"))
      (node (ref "U19") (pin "8") (pinfunction "VDD2_8") (pintype "power_in"))
      (node (ref "U2") (pin "2") (pinfunction "OUT_2") (pintype "power_in"))
      (node (ref "U2") (pin "4") (pinfunction "OUT_4") (pintype "power_in"))
    )
    (net (code "66") (name "unconnected-(U16-FBO-Pad5)") (class "Default")
      (node (ref "U16") (pin "5") (pinfunction "FBO_5") (pintype "output"))
    )
  )
)
